# MC_LV.net
KiCad netlist of a schematic drawn in Altium Designer
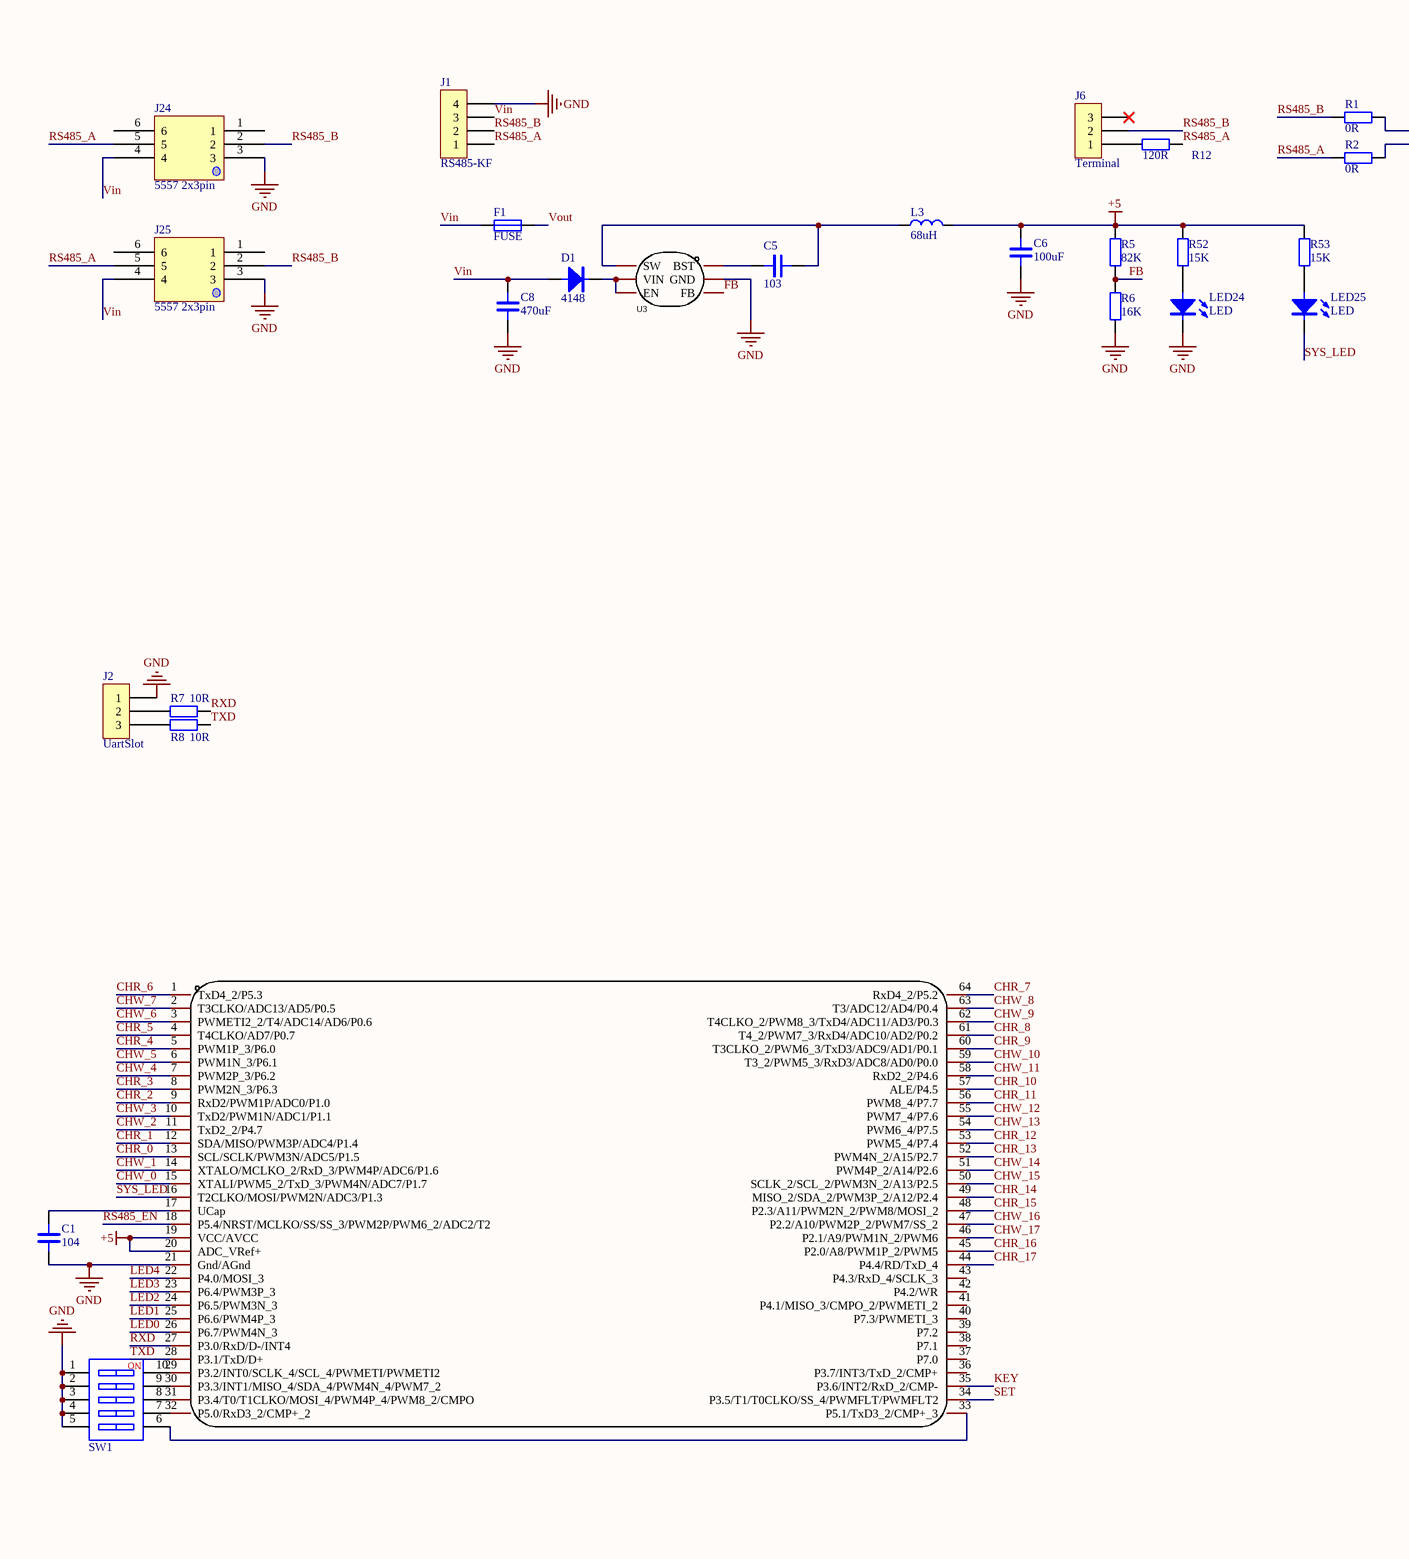
[diagram p0: MC_LV.SchDoc, left]
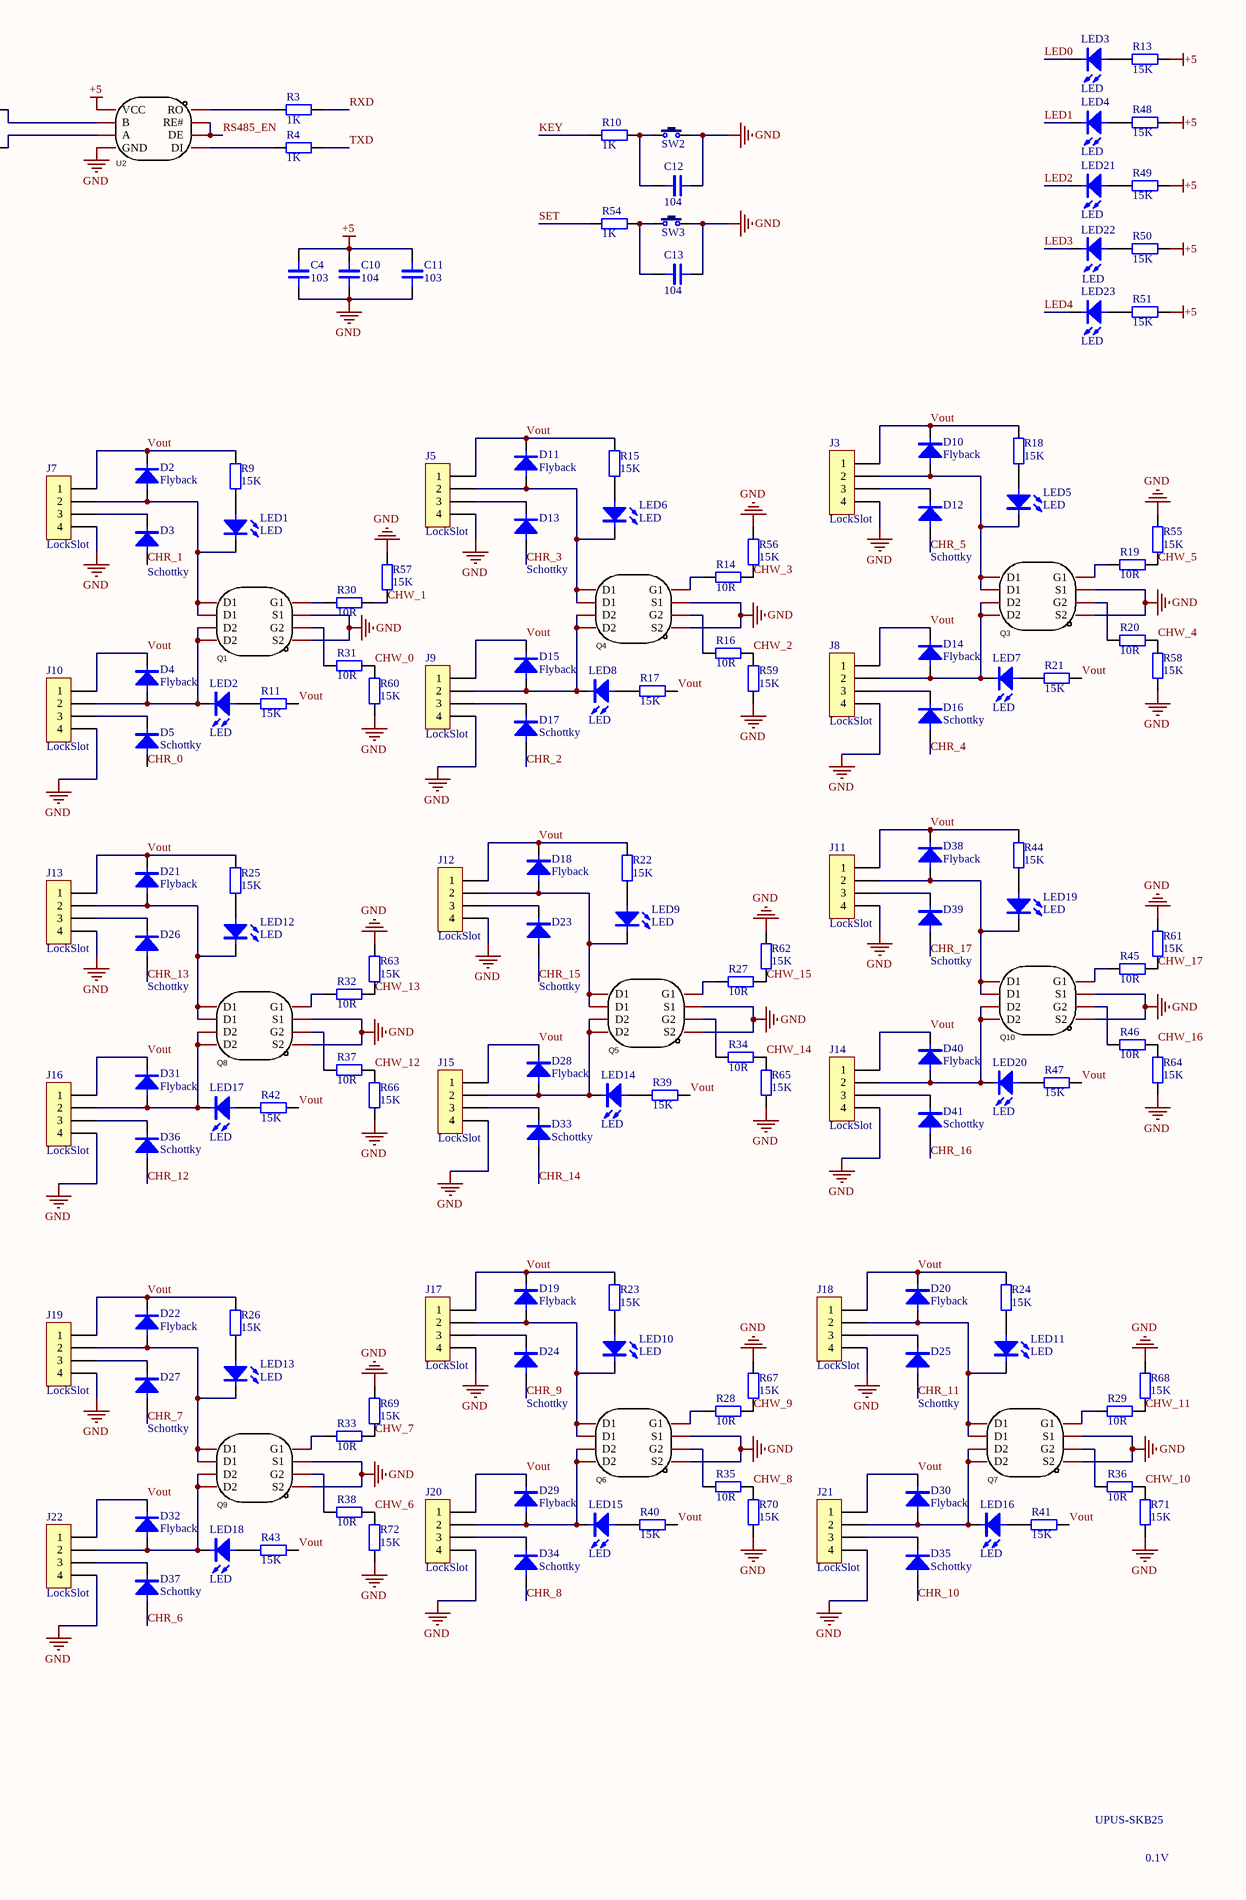
[diagram p1: MC_LV.SchDoc, right]

(export (version "E")
  (design (tool "Eeschema 10.0.6"))
  (components
    (comp (ref "C1")
      (value "104")
      (footprint "LC-0603_C")
      (description "Capacitor")
      (libsource (lib "General") (part "CAP"))
    )
    (comp (ref "C4")
      (value "103")
      (footprint "LC-0603_C")
      (description "Capacitor")
      (libsource (lib "General") (part "CAP"))
    )
    (comp (ref "C5")
      (value "103")
      (footprint "LC-0603_C")
      (description "Capacitor")
      (libsource (lib "General") (part "CAP"))
    )
    (comp (ref "C6")
      (value "100uF")
      (footprint "LC-1206_C")
      (description "Capacitor")
      (libsource (lib "General") (part "CAP"))
    )
    (comp (ref "C8")
      (value "470uF")
      (footprint "CM F(10*10.2)")
      (description "Capacitor")
      (libsource (lib "General") (part "CAP"))
    )
    (comp (ref "C10")
      (value "104")
      (footprint "LC-0603_C")
      (description "Capacitor")
      (libsource (lib "General") (part "CAP"))
    )
    (comp (ref "C11")
      (value "103")
      (footprint "LC-0603_C")
      (description "Capacitor")
      (libsource (lib "General") (part "CAP"))
    )
    (comp (ref "C12")
      (value "104")
      (footprint "LC-0603_C")
      (description "Capacitor")
      (libsource (lib "General") (part "CAP"))
    )
    (comp (ref "C13")
      (value "104")
      (footprint "LC-0603_C")
      (description "Capacitor")
      (libsource (lib "General") (part "CAP"))
    )
    (comp (ref "D1")
      (value "4148")
      (footprint "MINI_MELF (LL34)")
      (description "Diode")
      (libsource (lib "General") (part "ES2x"))
    )
    (comp (ref "D2")
      (value "Flyback")
      (footprint "SOD-123F")
      (description "Diode")
      (libsource (lib "General") (part "ES2x"))
    )
    (comp (ref "D3")
      (value "Schottky")
      (footprint "LC-SOD-523")
      (description "Diode")
      (libsource (lib "General") (part "ES2x"))
    )
    (comp (ref "D4")
      (value "Flyback")
      (footprint "SOD-123F")
      (description "Diode")
      (libsource (lib "General") (part "ES2x"))
    )
    (comp (ref "D5")
      (value "Schottky")
      (footprint "LC-SOD-523")
      (description "Diode")
      (libsource (lib "General") (part "ES2x"))
    )
    (comp (ref "D10")
      (value "Flyback")
      (footprint "SOD-123F")
      (description "Diode")
      (libsource (lib "General") (part "ES2x"))
    )
    (comp (ref "D11")
      (value "Flyback")
      (footprint "SOD-123F")
      (description "Diode")
      (libsource (lib "General") (part "ES2x"))
    )
    (comp (ref "D12")
      (value "Schottky")
      (footprint "LC-SOD-523")
      (description "Diode")
      (libsource (lib "General") (part "ES2x"))
    )
    (comp (ref "D13")
      (value "Schottky")
      (footprint "LC-SOD-523")
      (description "Diode")
      (libsource (lib "General") (part "ES2x"))
    )
    (comp (ref "D14")
      (value "Flyback")
      (footprint "SOD-123F")
      (description "Diode")
      (libsource (lib "General") (part "ES2x"))
    )
    (comp (ref "D15")
      (value "Flyback")
      (footprint "SOD-123F")
      (description "Diode")
      (libsource (lib "General") (part "ES2x"))
    )
    (comp (ref "D16")
      (value "Schottky")
      (footprint "LC-SOD-523")
      (description "Diode")
      (libsource (lib "General") (part "ES2x"))
    )
    (comp (ref "D17")
      (value "Schottky")
      (footprint "LC-SOD-523")
      (description "Diode")
      (libsource (lib "General") (part "ES2x"))
    )
    (comp (ref "D18")
      (value "Flyback")
      (footprint "SOD-123F")
      (description "Diode")
      (libsource (lib "General") (part "ES2x"))
    )
    (comp (ref "D19")
      (value "Flyback")
      (footprint "SOD-123F")
      (description "Diode")
      (libsource (lib "General") (part "ES2x"))
    )
    (comp (ref "D20")
      (value "Flyback")
      (footprint "SOD-123F")
      (description "Diode")
      (libsource (lib "General") (part "ES2x"))
    )
    (comp (ref "D21")
      (value "Flyback")
      (footprint "SOD-123F")
      (description "Diode")
      (libsource (lib "General") (part "ES2x"))
    )
    (comp (ref "D22")
      (value "Flyback")
      (footprint "SOD-123F")
      (description "Diode")
      (libsource (lib "General") (part "ES2x"))
    )
    (comp (ref "D23")
      (value "Schottky")
      (footprint "LC-SOD-523")
      (description "Diode")
      (libsource (lib "General") (part "ES2x"))
    )
    (comp (ref "D24")
      (value "Schottky")
      (footprint "LC-SOD-523")
      (description "Diode")
      (libsource (lib "General") (part "ES2x"))
    )
    (comp (ref "D25")
      (value "Schottky")
      (footprint "LC-SOD-523")
      (description "Diode")
      (libsource (lib "General") (part "ES2x"))
    )
    (comp (ref "D26")
      (value "Schottky")
      (footprint "LC-SOD-523")
      (description "Diode")
      (libsource (lib "General") (part "ES2x"))
    )
    (comp (ref "D27")
      (value "Schottky")
      (footprint "LC-SOD-523")
      (description "Diode")
      (libsource (lib "General") (part "ES2x"))
    )
    (comp (ref "D28")
      (value "Flyback")
      (footprint "SOD-123F")
      (description "Diode")
      (libsource (lib "General") (part "ES2x"))
    )
    (comp (ref "D29")
      (value "Flyback")
      (footprint "SOD-123F")
      (description "Diode")
      (libsource (lib "General") (part "ES2x"))
    )
    (comp (ref "D30")
      (value "Flyback")
      (footprint "SOD-123F")
      (description "Diode")
      (libsource (lib "General") (part "ES2x"))
    )
    (comp (ref "D31")
      (value "Flyback")
      (footprint "SOD-123F")
      (description "Diode")
      (libsource (lib "General") (part "ES2x"))
    )
    (comp (ref "D32")
      (value "Flyback")
      (footprint "SOD-123F")
      (description "Diode")
      (libsource (lib "General") (part "ES2x"))
    )
    (comp (ref "D33")
      (value "Schottky")
      (footprint "LC-SOD-523")
      (description "Diode")
      (libsource (lib "General") (part "ES2x"))
    )
    (comp (ref "D34")
      (value "Schottky")
      (footprint "LC-SOD-523")
      (description "Diode")
      (libsource (lib "General") (part "ES2x"))
    )
    (comp (ref "D35")
      (value "Schottky")
      (footprint "LC-SOD-523")
      (description "Diode")
      (libsource (lib "General") (part "ES2x"))
    )
    (comp (ref "D36")
      (value "Schottky")
      (footprint "LC-SOD-523")
      (description "Diode")
      (libsource (lib "General") (part "ES2x"))
    )
    (comp (ref "D37")
      (value "Schottky")
      (footprint "LC-SOD-523")
      (description "Diode")
      (libsource (lib "General") (part "ES2x"))
    )
    (comp (ref "D38")
      (value "Flyback")
      (footprint "SOD-123F")
      (description "Diode")
      (libsource (lib "General") (part "ES2x"))
    )
    (comp (ref "D39")
      (value "Schottky")
      (footprint "LC-SOD-523")
      (description "Diode")
      (libsource (lib "General") (part "ES2x"))
    )
    (comp (ref "D40")
      (value "Flyback")
      (footprint "SOD-123F")
      (description "Diode")
      (libsource (lib "General") (part "ES2x"))
    )
    (comp (ref "D41")
      (value "Schottky")
      (footprint "LC-SOD-523")
      (description "Diode")
      (libsource (lib "General") (part "ES2x"))
    )
    (comp (ref "F1")
      (value "FUSE")
      (footprint "FUSE-1812")
      (description "30V 3A")
      (libsource (lib "General") (part "FUSE"))
    )
    (comp (ref "J1")
      (value "RS485-KF")
      (footprint "KF128-5.08-4P")
      (description "Connector")
      (libsource (lib "") (part "HDR1x4_1"))
    )
    (comp (ref "J2")
      (value "UartSlot")
      (footprint "XH2.54-3P")
      (description "Connector")
      (libsource (lib "General") (part "HDR1x3"))
    )
    (comp (ref "J3")
      (value "LockSlot")
      (footprint "XH2.54-4P")
      (description "Connector")
      (libsource (lib "General") (part "HDR1x4"))
    )
    (comp (ref "J5")
      (value "LockSlot")
      (footprint "XH2.54-4P")
      (description "Connector")
      (libsource (lib "General") (part "HDR1x4"))
    )
    (comp (ref "J6")
      (value "Terminal")
      (footprint "PIN-3-2.54-1.0")
      (description "Connector")
      (libsource (lib "") (part "HDR1x3_1"))
    )
    (comp (ref "J7")
      (value "LockSlot")
      (footprint "XH2.54-4P")
      (description "Connector")
      (libsource (lib "General") (part "HDR1x4"))
    )
    (comp (ref "J8")
      (value "LockSlot")
      (footprint "XH2.54-4P")
      (description "Connector")
      (libsource (lib "General") (part "HDR1x4"))
    )
    (comp (ref "J9")
      (value "LockSlot")
      (footprint "XH2.54-4P")
      (description "Connector")
      (libsource (lib "General") (part "HDR1x4"))
    )
    (comp (ref "J10")
      (value "LockSlot")
      (footprint "XH2.54-4P")
      (description "Connector")
      (libsource (lib "General") (part "HDR1x4"))
    )
    (comp (ref "J11")
      (value "LockSlot")
      (footprint "XH2.54-4P")
      (description "Connector")
      (libsource (lib "General") (part "HDR1x4"))
    )
    (comp (ref "J12")
      (value "LockSlot")
      (footprint "XH2.54-4P")
      (description "Connector")
      (libsource (lib "General") (part "HDR1x4"))
    )
    (comp (ref "J13")
      (value "LockSlot")
      (footprint "XH2.54-4P")
      (description "Connector")
      (libsource (lib "General") (part "HDR1x4"))
    )
    (comp (ref "J14")
      (value "LockSlot")
      (footprint "XH2.54-4P")
      (description "Connector")
      (libsource (lib "General") (part "HDR1x4"))
    )
    (comp (ref "J15")
      (value "LockSlot")
      (footprint "XH2.54-4P")
      (description "Connector")
      (libsource (lib "General") (part "HDR1x4"))
    )
    (comp (ref "J16")
      (value "LockSlot")
      (footprint "XH2.54-4P")
      (description "Connector")
      (libsource (lib "General") (part "HDR1x4"))
    )
    (comp (ref "J17")
      (value "LockSlot")
      (footprint "XH2.54-4P")
      (description "Connector")
      (libsource (lib "General") (part "HDR1x4"))
    )
    (comp (ref "J18")
      (value "LockSlot")
      (footprint "XH2.54-4P")
      (description "Connector")
      (libsource (lib "General") (part "HDR1x4"))
    )
    (comp (ref "J19")
      (value "LockSlot")
      (footprint "XH2.54-4P")
      (description "Connector")
      (libsource (lib "General") (part "HDR1x4"))
    )
    (comp (ref "J20")
      (value "LockSlot")
      (footprint "XH2.54-4P")
      (description "Connector")
      (libsource (lib "General") (part "HDR1x4"))
    )
    (comp (ref "J21")
      (value "LockSlot")
      (footprint "XH2.54-4P")
      (description "Connector")
      (libsource (lib "General") (part "HDR1x4"))
    )
    (comp (ref "J22")
      (value "LockSlot")
      (footprint "XH2.54-4P")
      (description "Connector")
      (libsource (lib "General") (part "HDR1x4"))
    )
    (comp (ref "J24")
      (value "5557 2x3pin")
      (footprint "5557 2x3pin")
      (libsource (lib "General") (part "5557 2x3pin"))
    )
    (comp (ref "J25")
      (value "5557 2x3pin")
      (footprint "5557 2x3pin")
      (libsource (lib "General") (part "5557 2x3pin"))
    )
    (comp (ref "L3")
      (value "68uH")
      (footprint "CD32")
      (description "Inductance")
      (libsource (lib "General") (part "INDUCTANCE"))
    )
    (comp (ref "LED1") (value "LED") (footprint "LED 0603B") (libsource (lib "General") (part "LED")))
    (comp (ref "LED2") (value "LED") (footprint "LED 0603B") (libsource (lib "General") (part "LED")))
    (comp (ref "LED3") (value "LED") (footprint "LED 0603B") (libsource (lib "General") (part "LED")))
    (comp (ref "LED4") (value "LED") (footprint "LED 0603B") (libsource (lib "General") (part "LED")))
    (comp (ref "LED5") (value "LED") (footprint "LED 0603B") (libsource (lib "General") (part "LED")))
    (comp (ref "LED6") (value "LED") (footprint "LED 0603B") (libsource (lib "General") (part "LED")))
    (comp (ref "LED7") (value "LED") (footprint "LED 0603B") (libsource (lib "General") (part "LED")))
    (comp (ref "LED8") (value "LED") (footprint "LED 0603B") (libsource (lib "General") (part "LED")))
    (comp (ref "LED9") (value "LED") (footprint "LED 0603B") (libsource (lib "General") (part "LED")))
    (comp (ref "LED10") (value "LED") (footprint "LED 0603B") (libsource (lib "General") (part "LED")))
    (comp (ref "LED11") (value "LED") (footprint "LED 0603B") (libsource (lib "General") (part "LED")))
    (comp (ref "LED12") (value "LED") (footprint "LED 0603B") (libsource (lib "General") (part "LED")))
    (comp (ref "LED13") (value "LED") (footprint "LED 0603B") (libsource (lib "General") (part "LED")))
    (comp (ref "LED14") (value "LED") (footprint "LED 0603B") (libsource (lib "General") (part "LED")))
    (comp (ref "LED15") (value "LED") (footprint "LED 0603B") (libsource (lib "General") (part "LED")))
    (comp (ref "LED16") (value "LED") (footprint "LED 0603B") (libsource (lib "General") (part "LED")))
    (comp (ref "LED17") (value "LED") (footprint "LED 0603B") (libsource (lib "General") (part "LED")))
    (comp (ref "LED18") (value "LED") (footprint "LED 0603B") (libsource (lib "General") (part "LED")))
    (comp (ref "LED19") (value "LED") (footprint "LED 0603B") (libsource (lib "General") (part "LED")))
    (comp (ref "LED20") (value "LED") (footprint "LED 0603B") (libsource (lib "General") (part "LED")))
    (comp (ref "LED21") (value "LED") (footprint "LED 0603B") (libsource (lib "General") (part "LED")))
    (comp (ref "LED22") (value "LED") (footprint "LED 0603B") (libsource (lib "General") (part "LED")))
    (comp (ref "LED23") (value "LED") (footprint "LED 0603B") (libsource (lib "General") (part "LED")))
    (comp (ref "LED24") (value "LED") (footprint "LED 0603B") (libsource (lib "General") (part "LED")))
    (comp (ref "LED25") (value "LED") (footprint "LED 0603B") (libsource (lib "General") (part "LED")))
    (comp (ref "Q1")
      (value "NCE6005AS")
      (footprint "SOP8_N")
      (description "Mosfet")
      (fields (field (name "MANUFACTURER") "NCE(无锡新洁能)"))
      (libsource (lib "General") (part "NCE6005AS"))
    )
    (comp (ref "Q3")
      (value "NCE6005AS")
      (footprint "SOP8_N")
      (description "Mosfet")
      (fields (field (name "MANUFACTURER") "NCE(无锡新洁能)"))
      (libsource (lib "General") (part "NCE6005AS"))
    )
    (comp (ref "Q4")
      (value "NCE6005AS")
      (footprint "SOP8_N")
      (description "Mosfet")
      (fields (field (name "MANUFACTURER") "NCE(无锡新洁能)"))
      (libsource (lib "General") (part "NCE6005AS"))
    )
    (comp (ref "Q5")
      (value "NCE6005AS")
      (footprint "SOP8_N")
      (description "Mosfet")
      (fields (field (name "MANUFACTURER") "NCE(无锡新洁能)"))
      (libsource (lib "General") (part "NCE6005AS"))
    )
    (comp (ref "Q6")
      (value "NCE6005AS")
      (footprint "SOP8_N")
      (description "Mosfet")
      (fields (field (name "MANUFACTURER") "NCE(无锡新洁能)"))
      (libsource (lib "General") (part "NCE6005AS"))
    )
    (comp (ref "Q7")
      (value "NCE6005AS")
      (footprint "SOP8_N")
      (description "Mosfet")
      (fields (field (name "MANUFACTURER") "NCE(无锡新洁能)"))
      (libsource (lib "General") (part "NCE6005AS"))
    )
    (comp (ref "Q8")
      (value "NCE6005AS")
      (footprint "SOP8_N")
      (description "Mosfet")
      (fields (field (name "MANUFACTURER") "NCE(无锡新洁能)"))
      (libsource (lib "General") (part "NCE6005AS"))
    )
    (comp (ref "Q9")
      (value "NCE6005AS")
      (footprint "SOP8_N")
      (description "Mosfet")
      (fields (field (name "MANUFACTURER") "NCE(无锡新洁能)"))
      (libsource (lib "General") (part "NCE6005AS"))
    )
    (comp (ref "Q10")
      (value "NCE6005AS")
      (footprint "SOP8_N")
      (description "Mosfet")
      (fields (field (name "MANUFACTURER") "NCE(无锡新洁能)"))
      (libsource (lib "General") (part "NCE6005AS"))
    )
    (comp (ref "R1")
      (value "0R")
      (footprint "LC-0603_R")
      (description "Resistor")
      (libsource (lib "") (part "RES_3"))
    )
    (comp (ref "R2")
      (value "0R")
      (footprint "LC-0603_R")
      (description "Resistor")
      (libsource (lib "") (part "RES_3"))
    )
    (comp (ref "R3")
      (value "1K")
      (footprint "LC-0603_R")
      (description "Resistor")
      (libsource (lib "") (part "RES_3"))
    )
    (comp (ref "R4")
      (value "1K")
      (footprint "LC-0603_R")
      (description "Resistor")
      (libsource (lib "") (part "RES_3"))
    )
    (comp (ref "R5")
      (value "82K")
      (footprint "LC-0603_R")
      (description "Resistor")
      (libsource (lib "") (part "RES_1"))
    )
    (comp (ref "R6")
      (value "16K")
      (footprint "LC-0603_R")
      (description "Resistor")
      (libsource (lib "") (part "RES_1"))
    )
    (comp (ref "R7")
      (value "10R")
      (footprint "LC-0603_R")
      (description "Resistor")
      (libsource (lib "") (part "RES_3"))
    )
    (comp (ref "R8")
      (value "10R")
      (footprint "LC-0603_R")
      (description "Resistor")
      (libsource (lib "") (part "RES_3"))
    )
    (comp (ref "R9")
      (value "15K")
      (footprint "LC-0603_R")
      (description "Resistor")
      (libsource (lib "") (part "RES_1"))
    )
    (comp (ref "R10")
      (value "1K")
      (footprint "LC-0603_R")
      (description "Resistor")
      (libsource (lib "General") (part "RES"))
    )
    (comp (ref "R11")
      (value "15K")
      (footprint "LC-0603_R")
      (description "Resistor")
      (libsource (lib "") (part "RES_3"))
    )
    (comp (ref "R12")
      (value "120R")
      (footprint "LC-0603_R")
      (description "Resistor")
      (libsource (lib "") (part "RES_2"))
    )
    (comp (ref "R13")
      (value "15K")
      (footprint "LC-0603_R")
      (description "Resistor")
      (libsource (lib "") (part "RES_3"))
    )
    (comp (ref "R14")
      (value "10R")
      (footprint "LC-0603_R")
      (description "Resistor")
      (libsource (lib "") (part "RES_2"))
    )
    (comp (ref "R15")
      (value "15K")
      (footprint "LC-0603_R")
      (description "Resistor")
      (libsource (lib "") (part "RES_1"))
    )
    (comp (ref "R16")
      (value "10R")
      (footprint "LC-0603_R")
      (description "Resistor")
      (libsource (lib "") (part "RES_2"))
    )
    (comp (ref "R17")
      (value "15K")
      (footprint "LC-0603_R")
      (description "Resistor")
      (libsource (lib "") (part "RES_3"))
    )
    (comp (ref "R18")
      (value "15K")
      (footprint "LC-0603_R")
      (description "Resistor")
      (libsource (lib "") (part "RES_1"))
    )
    (comp (ref "R19")
      (value "10R")
      (footprint "LC-0603_R")
      (description "Resistor")
      (libsource (lib "") (part "RES_2"))
    )
    (comp (ref "R20")
      (value "10R")
      (footprint "LC-0603_R")
      (description "Resistor")
      (libsource (lib "") (part "RES_2"))
    )
    (comp (ref "R21")
      (value "15K")
      (footprint "LC-0603_R")
      (description "Resistor")
      (libsource (lib "") (part "RES_3"))
    )
    (comp (ref "R22")
      (value "15K")
      (footprint "LC-0603_R")
      (description "Resistor")
      (libsource (lib "") (part "RES_1"))
    )
    (comp (ref "R23")
      (value "15K")
      (footprint "LC-0603_R")
      (description "Resistor")
      (libsource (lib "") (part "RES_1"))
    )
    (comp (ref "R24")
      (value "15K")
      (footprint "LC-0603_R")
      (description "Resistor")
      (libsource (lib "") (part "RES_1"))
    )
    (comp (ref "R25")
      (value "15K")
      (footprint "LC-0603_R")
      (description "Resistor")
      (libsource (lib "") (part "RES_1"))
    )
    (comp (ref "R26")
      (value "15K")
      (footprint "LC-0603_R")
      (description "Resistor")
      (libsource (lib "") (part "RES_1"))
    )
    (comp (ref "R27")
      (value "10R")
      (footprint "LC-0603_R")
      (description "Resistor")
      (libsource (lib "") (part "RES_2"))
    )
    (comp (ref "R28")
      (value "10R")
      (footprint "LC-0603_R")
      (description "Resistor")
      (libsource (lib "") (part "RES_2"))
    )
    (comp (ref "R29")
      (value "10R")
      (footprint "LC-0603_R")
      (description "Resistor")
      (libsource (lib "") (part "RES_2"))
    )
    (comp (ref "R30")
      (value "10R")
      (footprint "LC-0603_R")
      (description "Resistor")
      (libsource (lib "") (part "RES_2"))
    )
    (comp (ref "R31")
      (value "10R")
      (footprint "LC-0603_R")
      (description "Resistor")
      (libsource (lib "") (part "RES_3"))
    )
    (comp (ref "R32")
      (value "10R")
      (footprint "LC-0603_R")
      (description "Resistor")
      (libsource (lib "") (part "RES_2"))
    )
    (comp (ref "R33")
      (value "10R")
      (footprint "LC-0603_R")
      (description "Resistor")
      (libsource (lib "") (part "RES_2"))
    )
    (comp (ref "R34")
      (value "10R")
      (footprint "LC-0603_R")
      (description "Resistor")
      (libsource (lib "") (part "RES_2"))
    )
    (comp (ref "R35")
      (value "10R")
      (footprint "LC-0603_R")
      (description "Resistor")
      (libsource (lib "") (part "RES_2"))
    )
    (comp (ref "R36")
      (value "10R")
      (footprint "LC-0603_R")
      (description "Resistor")
      (libsource (lib "") (part "RES_2"))
    )
    (comp (ref "R37")
      (value "10R")
      (footprint "LC-0603_R")
      (description "Resistor")
      (libsource (lib "") (part "RES_2"))
    )
    (comp (ref "R38")
      (value "10R")
      (footprint "LC-0603_R")
      (description "Resistor")
      (libsource (lib "") (part "RES_2"))
    )
    (comp (ref "R39")
      (value "15K")
      (footprint "LC-0603_R")
      (description "Resistor")
      (libsource (lib "") (part "RES_3"))
    )
    (comp (ref "R40")
      (value "15K")
      (footprint "LC-0603_R")
      (description "Resistor")
      (libsource (lib "") (part "RES_3"))
    )
    (comp (ref "R41")
      (value "15K")
      (footprint "LC-0603_R")
      (description "Resistor")
      (libsource (lib "") (part "RES_3"))
    )
    (comp (ref "R42")
      (value "15K")
      (footprint "LC-0603_R")
      (description "Resistor")
      (libsource (lib "") (part "RES_3"))
    )
    (comp (ref "R43")
      (value "15K")
      (footprint "LC-0603_R")
      (description "Resistor")
      (libsource (lib "") (part "RES_3"))
    )
    (comp (ref "R44")
      (value "15K")
      (footprint "LC-0603_R")
      (description "Resistor")
      (libsource (lib "") (part "RES_1"))
    )
    (comp (ref "R45")
      (value "10R")
      (footprint "LC-0603_R")
      (description "Resistor")
      (libsource (lib "") (part "RES_2"))
    )
    (comp (ref "R46")
      (value "10R")
      (footprint "LC-0603_R")
      (description "Resistor")
      (libsource (lib "") (part "RES_2"))
    )
    (comp (ref "R47")
      (value "15K")
      (footprint "LC-0603_R")
      (description "Resistor")
      (libsource (lib "") (part "RES_3"))
    )
    (comp (ref "R48")
      (value "15K")
      (footprint "LC-0603_R")
      (description "Resistor")
      (libsource (lib "") (part "RES_3"))
    )
    (comp (ref "R49")
      (value "15K")
      (footprint "LC-0603_R")
      (description "Resistor")
      (libsource (lib "") (part "RES_3"))
    )
    (comp (ref "R50")
      (value "15K")
      (footprint "LC-0603_R")
      (description "Resistor")
      (libsource (lib "") (part "RES_3"))
    )
    (comp (ref "R51")
      (value "15K")
      (footprint "LC-0603_R")
      (description "Resistor")
      (libsource (lib "") (part "RES_3"))
    )
    (comp (ref "R52")
      (value "15K")
      (footprint "LC-0603_R")
      (description "Resistor")
      (libsource (lib "") (part "RES_1"))
    )
    (comp (ref "R53")
      (value "15K")
      (footprint "LC-0603_R")
      (description "Resistor")
      (libsource (lib "") (part "RES_1"))
    )
    (comp (ref "R54")
      (value "1K")
      (footprint "LC-0603_R")
      (description "Resistor")
      (libsource (lib "General") (part "RES"))
    )
    (comp (ref "R55")
      (value "15K")
      (footprint "LC-0603_R")
      (description "Resistor")
      (libsource (lib "General") (part "RES"))
    )
    (comp (ref "R56")
      (value "15K")
      (footprint "LC-0603_R")
      (description "Resistor")
      (libsource (lib "General") (part "RES"))
    )
    (comp (ref "R57")
      (value "15K")
      (footprint "LC-0603_R")
      (description "Resistor")
      (libsource (lib "General") (part "RES"))
    )
    (comp (ref "R58")
      (value "15K")
      (footprint "LC-0603_R")
      (description "Resistor")
      (libsource (lib "") (part "RES_1"))
    )
    (comp (ref "R59")
      (value "15K")
      (footprint "LC-0603_R")
      (description "Resistor")
      (libsource (lib "") (part "RES_1"))
    )
    (comp (ref "R60")
      (value "15K")
      (footprint "LC-0603_R")
      (description "Resistor")
      (libsource (lib "") (part "RES_1"))
    )
    (comp (ref "R61")
      (value "15K")
      (footprint "LC-0603_R")
      (description "Resistor")
      (libsource (lib "General") (part "RES"))
    )
    (comp (ref "R62")
      (value "15K")
      (footprint "LC-0603_R")
      (description "Resistor")
      (libsource (lib "General") (part "RES"))
    )
    (comp (ref "R63")
      (value "15K")
      (footprint "LC-0603_R")
      (description "Resistor")
      (libsource (lib "General") (part "RES"))
    )
    (comp (ref "R64")
      (value "15K")
      (footprint "LC-0603_R")
      (description "Resistor")
      (libsource (lib "") (part "RES_1"))
    )
    (comp (ref "R65")
      (value "15K")
      (footprint "LC-0603_R")
      (description "Resistor")
      (libsource (lib "") (part "RES_1"))
    )
    (comp (ref "R66")
      (value "15K")
      (footprint "LC-0603_R")
      (description "Resistor")
      (libsource (lib "") (part "RES_1"))
    )
    (comp (ref "R67")
      (value "15K")
      (footprint "LC-0603_R")
      (description "Resistor")
      (libsource (lib "General") (part "RES"))
    )
    (comp (ref "R68")
      (value "15K")
      (footprint "LC-0603_R")
      (description "Resistor")
      (libsource (lib "General") (part "RES"))
    )
    (comp (ref "R69")
      (value "15K")
      (footprint "LC-0603_R")
      (description "Resistor")
      (libsource (lib "General") (part "RES"))
    )
    (comp (ref "R70")
      (value "15K")
      (footprint "LC-0603_R")
      (description "Resistor")
      (libsource (lib "") (part "RES_1"))
    )
    (comp (ref "R71")
      (value "15K")
      (footprint "LC-0603_R")
      (description "Resistor")
      (libsource (lib "") (part "RES_1"))
    )
    (comp (ref "R72")
      (value "15K")
      (footprint "LC-0603_R")
      (description "Resistor")
      (libsource (lib "") (part "RES_1"))
    )
    (comp (ref "SW1")
      (value "CSW-5P")
      (footprint "SMD-5KEY")
      (description "5路编码开关")
      (fields (field (name "版权归属") "源创客"))
      (libsource (lib "按键-开关") (part "CSW-5P"))
    )
    (comp (ref "SW2")
      (value "3x6x5")
      (footprint "TSW SMD-3*6*2.5")
      (description "3x6轻触开关")
      (fields (field (name "版权归属") "源创客"))
      (libsource (lib "按键-开关") (part "TSW 3x6"))
    )
    (comp (ref "SW3")
      (value "3x6x5")
      (footprint "TSW SMD-3*6*2.5")
      (description "3x6轻触开关")
      (fields (field (name "版权归属") "源创客"))
      (libsource (lib "按键-开关") (part "TSW 3x6"))
    )
    (comp (ref "U1")
      (value "STC8H8K64U-45I-LQFP64_C3013146")
      (footprint "LQFP64 10x10_N")
      (description "MCU")
      (fields
        (field (name "MANUFACTURER") "STC(宏晶)")
        (field (name "MANUFACTURER PART") "STC8H8K64U-45I-LQFP64")
      )
      (libsource (lib "General") (part "STC8H8K64U-45I-LQFP64_C3013146"))
    )
    (comp (ref "U2")
      (value "YD3082EESA")
      (footprint "SOP8_N")
      (description "RS485 Controller")
      (fields (field (name "MANUFACTURER") "GATEMODE(捷茂微)"))
      (libsource (lib "General") (part "YD3082EESA"))
    )
    (comp (ref "U3")
      (value "LGS5145")
      (footprint "SOT23-6L")
      (description "DC-DC")
      (fields (field (name "MANUFACTURER") "Legend-Si(棱晶半导体)"))
      (libsource (lib "General") (part "LGS5145"))
    )
  )
  (nets
    (net (code "1") (name "+5") (class "Default")
      (node (ref "C10") (pin "1") (pinfunction "1_1") (pintype "passive"))
      (node (ref "C11") (pin "1") (pinfunction "1_1") (pintype "passive"))
      (node (ref "C4") (pin "1") (pinfunction "1_1") (pintype "passive"))
      (node (ref "C6") (pin "1") (pinfunction "1_1") (pintype "passive"))
      (node (ref "L3") (pin "2") (pinfunction "2_2") (pintype "passive"))
      (node (ref "R13") (pin "2") (pinfunction "2_2") (pintype "passive"))
      (node (ref "R48") (pin "2") (pinfunction "2_2") (pintype "passive"))
      (node (ref "R49") (pin "2") (pinfunction "2_2") (pintype "passive"))
      (node (ref "R5") (pin "2") (pinfunction "2_2") (pintype "passive"))
      (node (ref "R50") (pin "2") (pinfunction "2_2") (pintype "passive"))
      (node (ref "R51") (pin "2") (pinfunction "2_2") (pintype "passive"))
      (node (ref "R52") (pin "2") (pinfunction "2_2") (pintype "passive"))
      (node (ref "R53") (pin "2") (pinfunction "2_2") (pintype "passive"))
      (node (ref "U1") (pin "19") (pinfunction "VCC/AVCC_19") (pintype "passive"))
      (node (ref "U1") (pin "20") (pinfunction "ADC_VRef+_20") (pintype "passive"))
      (node (ref "U2") (pin "8") (pinfunction "VCC_8") (pintype "passive"))
    )
    (net (code "2") (name "/CHR_0") (class "Default")
      (node (ref "D5") (pin "1") (pinfunction "A_1") (pintype "passive"))
      (node (ref "U1") (pin "13") (pinfunction "SCL/SCLK/PWM3N/ADC5/P1.5_13") (pintype "passive"))
    )
    (net (code "3") (name "/CHR_1") (class "Default")
      (node (ref "D3") (pin "1") (pinfunction "A_1") (pintype "passive"))
      (node (ref "U1") (pin "12") (pinfunction "SDA/MISO/PWM3P/ADC4/P1.4_12") (pintype "passive"))
    )
    (net (code "4") (name "/CHR_2") (class "Default")
      (node (ref "D17") (pin "1") (pinfunction "A_1") (pintype "passive"))
      (node (ref "U1") (pin "9") (pinfunction "RxD2/PWM1P/ADC0/P1.0_9") (pintype "passive"))
    )
    (net (code "5") (name "/CHR_3") (class "Default")
      (node (ref "D13") (pin "1") (pinfunction "A_1") (pintype "passive"))
      (node (ref "U1") (pin "8") (pinfunction "PWM2N_3/P6.3_8") (pintype "passive"))
    )
    (net (code "6") (name "/CHR_4") (class "Default")
      (node (ref "D16") (pin "1") (pinfunction "A_1") (pintype "passive"))
      (node (ref "U1") (pin "5") (pinfunction "PWM1P_3/P6.0_5") (pintype "passive"))
    )
    (net (code "7") (name "/CHR_5") (class "Default")
      (node (ref "D12") (pin "1") (pinfunction "A_1") (pintype "passive"))
      (node (ref "U1") (pin "4") (pinfunction "T4CLKO/AD7/P0.7_4") (pintype "passive"))
    )
    (net (code "8") (name "/CHR_6") (class "Default")
      (node (ref "D37") (pin "1") (pinfunction "A_1") (pintype "passive"))
      (node (ref "U1") (pin "1") (pinfunction "TxD4_2/P5.3_1") (pintype "passive"))
    )
    (net (code "9") (name "/CHR_7") (class "Default")
      (node (ref "D27") (pin "1") (pinfunction "A_1") (pintype "passive"))
      (node (ref "U1") (pin "64") (pinfunction "RxD4_2/P5.2_64") (pintype "passive"))
    )
    (net (code "10") (name "/CHR_8") (class "Default")
      (node (ref "D34") (pin "1") (pinfunction "A_1") (pintype "passive"))
      (node (ref "U1") (pin "61") (pinfunction "T4_2/PWM7_3/RxD4/ADC10/AD2/P0.2_61") (pintype "passive"))
    )
    (net (code "11") (name "/CHR_9") (class "Default")
      (node (ref "D24") (pin "1") (pinfunction "A_1") (pintype "passive"))
      (node (ref "U1") (pin "60") (pinfunction "T3CLKO_2/PWM6_3/TxD3/ADC9/AD1/P0.1_60") (pintype "passive"))
    )
    (net (code "12") (name "/CHR_10") (class "Default")
      (node (ref "D35") (pin "1") (pinfunction "A_1") (pintype "passive"))
      (node (ref "U1") (pin "57") (pinfunction "ALE/P4.5_57") (pintype "passive"))
    )
    (net (code "13") (name "/CHR_11") (class "Default")
      (node (ref "D25") (pin "1") (pinfunction "A_1") (pintype "passive"))
      (node (ref "U1") (pin "56") (pinfunction "PWM8_4/P7.7_56") (pintype "passive"))
    )
    (net (code "14") (name "/CHR_12") (class "Default")
      (node (ref "D36") (pin "1") (pinfunction "A_1") (pintype "passive"))
      (node (ref "U1") (pin "53") (pinfunction "PWM5_4/P7.4_53") (pintype "passive"))
    )
    (net (code "15") (name "/CHR_13") (class "Default")
      (node (ref "D26") (pin "1") (pinfunction "A_1") (pintype "passive"))
      (node (ref "U1") (pin "52") (pinfunction "PWM4N_2/A15/P2.7_52") (pintype "passive"))
    )
    (net (code "16") (name "/CHR_14") (class "Default")
      (node (ref "D33") (pin "1") (pinfunction "A_1") (pintype "passive"))
      (node (ref "U1") (pin "49") (pinfunction "MISO_2/SDA_2/PWM3P_2/A12/P2.4_49") (pintype "passive"))
    )
    (net (code "17") (name "/CHR_15") (class "Default")
      (node (ref "D23") (pin "1") (pinfunction "A_1") (pintype "passive"))
      (node (ref "U1") (pin "48") (pinfunction "P2.3/A11/PWM2N_2/PWM8/MOSI_2_48") (pintype "passive"))
    )
    (net (code "18") (name "/CHR_16") (class "Default")
      (node (ref "D41") (pin "1") (pinfunction "A_1") (pintype "passive"))
      (node (ref "U1") (pin "45") (pinfunction "P2.0/A8/PWM1P_2/PWM5_45") (pintype "passive"))
    )
    (net (code "19") (name "/CHR_17") (class "Default")
      (node (ref "D39") (pin "1") (pinfunction "A_1") (pintype "passive"))
      (node (ref "U1") (pin "44") (pinfunction "P4.4/RD/TxD_4_44") (pintype "passive"))
    )
    (net (code "20") (name "/CHW_0") (class "Default")
      (node (ref "R31") (pin "2") (pinfunction "2_2") (pintype "passive"))
      (node (ref "R60") (pin "2") (pinfunction "2_2") (pintype "passive"))
      (node (ref "U1") (pin "15") (pinfunction "XTALI/PWM5_2/TxD_3/PWM4N/ADC7/P1.7_15") (pintype "passive"))
    )
    (net (code "21") (name "/CHW_1") (class "Default")
      (node (ref "R30") (pin "1") (pinfunction "1_1") (pintype "passive"))
      (node (ref "R57") (pin "2") (pinfunction "2_2") (pintype "passive"))
      (node (ref "U1") (pin "14") (pinfunction "XTALO/MCLKO_2/RxD_3/PWM4P/ADC6/P1.6_14") (pintype "passive"))
    )
    (net (code "22") (name "/CHW_2") (class "Default")
      (node (ref "R16") (pin "1") (pinfunction "1_1") (pintype "passive"))
      (node (ref "R59") (pin "2") (pinfunction "2_2") (pintype "passive"))
      (node (ref "U1") (pin "11") (pinfunction "TxD2_2/P4.7_11") (pintype "passive"))
    )
    (net (code "23") (name "/CHW_3") (class "Default")
      (node (ref "R14") (pin "1") (pinfunction "1_1") (pintype "passive"))
      (node (ref "R56") (pin "2") (pinfunction "2_2") (pintype "passive"))
      (node (ref "U1") (pin "10") (pinfunction "TxD2/PWM1N/ADC1/P1.1_10") (pintype "passive"))
    )
    (net (code "24") (name "/CHW_4") (class "Default")
      (node (ref "R20") (pin "1") (pinfunction "1_1") (pintype "passive"))
      (node (ref "R58") (pin "2") (pinfunction "2_2") (pintype "passive"))
      (node (ref "U1") (pin "7") (pinfunction "PWM2P_3/P6.2_7") (pintype "passive"))
    )
    (net (code "25") (name "/CHW_5") (class "Default")
      (node (ref "R19") (pin "1") (pinfunction "1_1") (pintype "passive"))
      (node (ref "R55") (pin "2") (pinfunction "2_2") (pintype "passive"))
      (node (ref "U1") (pin "6") (pinfunction "PWM1N_3/P6.1_6") (pintype "passive"))
    )
    (net (code "26") (name "/CHW_6") (class "Default")
      (node (ref "R38") (pin "1") (pinfunction "1_1") (pintype "passive"))
      (node (ref "R72") (pin "2") (pinfunction "2_2") (pintype "passive"))
      (node (ref "U1") (pin "3") (pinfunction "PWMETI2_2/T4/ADC14/AD6/P0.6_3") (pintype "passive"))
    )
    (net (code "27") (name "/CHW_7") (class "Default")
      (node (ref "R33") (pin "1") (pinfunction "1_1") (pintype "passive"))
      (node (ref "R69") (pin "2") (pinfunction "2_2") (pintype "passive"))
      (node (ref "U1") (pin "2") (pinfunction "T3CLKO/ADC13/AD5/P0.5_2") (pintype "passive"))
    )
    (net (code "28") (name "/CHW_8") (class "Default")
      (node (ref "R35") (pin "1") (pinfunction "1_1") (pintype "passive"))
      (node (ref "R70") (pin "2") (pinfunction "2_2") (pintype "passive"))
      (node (ref "U1") (pin "63") (pinfunction "T3/ADC12/AD4/P0.4_63") (pintype "passive"))
    )
    (net (code "29") (name "/CHW_9") (class "Default")
      (node (ref "R28") (pin "1") (pinfunction "1_1") (pintype "passive"))
      (node (ref "R67") (pin "2") (pinfunction "2_2") (pintype "passive"))
      (node (ref "U1") (pin "62") (pinfunction "T4CLKO_2/PWM8_3/TxD4/ADC11/AD3/P0.3_62") (pintype "passive"))
    )
    (net (code "30") (name "/CHW_10") (class "Default")
      (node (ref "R36") (pin "1") (pinfunction "1_1") (pintype "passive"))
      (node (ref "R71") (pin "2") (pinfunction "2_2") (pintype "passive"))
      (node (ref "U1") (pin "59") (pinfunction "T3_2/PWM5_3/RxD3/ADC8/AD0/P0.0_59") (pintype "passive"))
    )
    (net (code "31") (name "/CHW_11") (class "Default")
      (node (ref "R29") (pin "1") (pinfunction "1_1") (pintype "passive"))
      (node (ref "R68") (pin "2") (pinfunction "2_2") (pintype "passive"))
      (node (ref "U1") (pin "58") (pinfunction "RxD2_2/P4.6_58") (pintype "passive"))
    )
    (net (code "32") (name "/CHW_12") (class "Default")
      (node (ref "R37") (pin "1") (pinfunction "1_1") (pintype "passive"))
      (node (ref "R66") (pin "2") (pinfunction "2_2") (pintype "passive"))
      (node (ref "U1") (pin "55") (pinfunction "PWM7_4/P7.6_55") (pintype "passive"))
    )
    (net (code "33") (name "/CHW_13") (class "Default")
      (node (ref "R32") (pin "1") (pinfunction "1_1") (pintype "passive"))
      (node (ref "R63") (pin "2") (pinfunction "2_2") (pintype "passive"))
      (node (ref "U1") (pin "54") (pinfunction "PWM6_4/P7.5_54") (pintype "passive"))
    )
    (net (code "34") (name "/CHW_14") (class "Default")
      (node (ref "R34") (pin "1") (pinfunction "1_1") (pintype "passive"))
      (node (ref "R65") (pin "2") (pinfunction "2_2") (pintype "passive"))
      (node (ref "U1") (pin "51") (pinfunction "PWM4P_2/A14/P2.6_51") (pintype "passive"))
    )
    (net (code "35") (name "/CHW_15") (class "Default")
      (node (ref "R27") (pin "1") (pinfunction "1_1") (pintype "passive"))
      (node (ref "R62") (pin "2") (pinfunction "2_2") (pintype "passive"))
      (node (ref "U1") (pin "50") (pinfunction "SCLK_2/SCL_2/PWM3N_2/A13/P2.5_50") (pintype "passive"))
    )
    (net (code "36") (name "/CHW_16") (class "Default")
      (node (ref "R46") (pin "1") (pinfunction "1_1") (pintype "passive"))
      (node (ref "R64") (pin "2") (pinfunction "2_2") (pintype "passive"))
      (node (ref "U1") (pin "47") (pinfunction "P2.2/A10/PWM2P_2/PWM7/SS_2_47") (pintype "passive"))
    )
    (net (code "37") (name "/CHW_17") (class "Default")
      (node (ref "R45") (pin "1") (pinfunction "1_1") (pintype "passive"))
      (node (ref "R61") (pin "2") (pinfunction "2_2") (pintype "passive"))
      (node (ref "U1") (pin "46") (pinfunction "P2.1/A9/PWM1N_2/PWM6_46") (pintype "passive"))
    )
    (net (code "38") (name "/FB") (class "Default")
      (node (ref "R5") (pin "1") (pinfunction "1_1") (pintype "passive"))
      (node (ref "R6") (pin "2") (pinfunction "2_2") (pintype "passive"))
      (node (ref "U3") (pin "3") (pinfunction "FB_3") (pintype "passive"))
    )
    (net (code "39") (name "/KEY") (class "Default")
      (node (ref "R10") (pin "2") (pinfunction "2_2") (pintype "passive"))
      (node (ref "U1") (pin "35") (pinfunction "P3.6/INT2/RxD_2/CMP-_35") (pintype "passive"))
    )
    (net (code "40") (name "/LED0") (class "Default")
      (node (ref "LED3") (pin "2") (pinfunction "C_2") (pintype "passive"))
      (node (ref "U1") (pin "26") (pinfunction "P6.7/PWM4N_3_26") (pintype "passive"))
    )
    (net (code "41") (name "/LED1") (class "Default")
      (node (ref "LED4") (pin "2") (pinfunction "C_2") (pintype "passive"))
      (node (ref "U1") (pin "25") (pinfunction "P6.6/PWM4P_3_25") (pintype "passive"))
    )
    (net (code "42") (name "/LED2") (class "Default")
      (node (ref "LED21") (pin "2") (pinfunction "C_2") (pintype "passive"))
      (node (ref "U1") (pin "24") (pinfunction "P6.5/PWM3N_3_24") (pintype "passive"))
    )
    (net (code "43") (name "/LED3") (class "Default")
      (node (ref "LED22") (pin "2") (pinfunction "C_2") (pintype "passive"))
      (node (ref "U1") (pin "23") (pinfunction "P6.4/PWM3P_3_23") (pintype "passive"))
    )
    (net (code "44") (name "/LED4") (class "Default")
      (node (ref "LED23") (pin "2") (pinfunction "C_2") (pintype "passive"))
      (node (ref "U1") (pin "22") (pinfunction "P4.0/MOSI_3_22") (pintype "passive"))
    )
    (net (code "45") (name "/RS485_A") (class "Default")
      (node (ref "J1") (pin "1") (pinfunction "1_1") (pintype "passive"))
      (node (ref "J24") (pin "5") (pinfunction "5_5") (pintype "passive"))
      (node (ref "J25") (pin "5") (pinfunction "5_5") (pintype "passive"))
      (node (ref "R12") (pin "1") (pinfunction "1_1") (pintype "passive"))
      (node (ref "R2") (pin "1") (pinfunction "1_1") (pintype "passive"))
    )
    (net (code "46") (name "/RS485_B") (class "Default")
      (node (ref "J1") (pin "2") (pinfunction "2_2") (pintype "passive"))
      (node (ref "J24") (pin "2") (pinfunction "2_2") (pintype "passive"))
      (node (ref "J25") (pin "2") (pinfunction "2_2") (pintype "passive"))
      (node (ref "J6") (pin "2") (pinfunction "2_2") (pintype "passive"))
      (node (ref "R1") (pin "1") (pinfunction "1_1") (pintype "passive"))
    )
    (net (code "47") (name "/RS485_EN") (class "Default")
      (node (ref "U1") (pin "18") (pinfunction "P5.4/NRST/MCLKO/SS/SS_3/PWM2P/PWM6_2/ADC2/T2_18") (pintype "passive"))
      (node (ref "U2") (pin "2") (pinfunction "RE#_2") (pintype "passive"))
      (node (ref "U2") (pin "3") (pinfunction "DE_3") (pintype "passive"))
    )
    (net (code "48") (name "/RXD") (class "Default")
      (node (ref "R3") (pin "2") (pinfunction "2_2") (pintype "passive"))
      (node (ref "R7") (pin "2") (pinfunction "2_2") (pintype "passive"))
      (node (ref "U1") (pin "27") (pinfunction "P3.0/RxD/D-/INT4_27") (pintype "passive"))
    )
    (net (code "49") (name "/SET") (class "Default")
      (node (ref "R54") (pin "2") (pinfunction "2_2") (pintype "passive"))
      (node (ref "U1") (pin "34") (pinfunction "P3.5/T1/T0CLKO/SS_4/PWMFLT/PWMFLT2_34") (pintype "passive"))
    )
    (net (code "50") (name "/SYS_LED") (class "Default")
      (node (ref "LED25") (pin "2") (pinfunction "C_2") (pintype "passive"))
      (node (ref "U1") (pin "16") (pinfunction "T2CLKO/MOSI/PWM2N/ADC3/P1.3_16") (pintype "passive"))
    )
    (net (code "51") (name "/TXD") (class "Default")
      (node (ref "R4") (pin "2") (pinfunction "2_2") (pintype "passive"))
      (node (ref "R8") (pin "2") (pinfunction "2_2") (pintype "passive"))
      (node (ref "U1") (pin "28") (pinfunction "P3.1/TxD/D+_28") (pintype "passive"))
    )
    (net (code "52") (name "/Vin") (class "Default")
      (node (ref "C8") (pin "1") (pinfunction "1_1") (pintype "passive"))
      (node (ref "D1") (pin "1") (pinfunction "A_1") (pintype "passive"))
      (node (ref "F1") (pin "1") (pinfunction "1_1") (pintype "passive"))
      (node (ref "J1") (pin "3") (pinfunction "3_3") (pintype "passive"))
      (node (ref "J24") (pin "4") (pinfunction "4_4") (pintype "passive"))
      (node (ref "J25") (pin "4") (pinfunction "4_4") (pintype "passive"))
    )
    (net (code "53") (name "/Vout") (class "Default")
      (node (ref "D10") (pin "2") (pinfunction "C_2") (pintype "passive"))
      (node (ref "D11") (pin "2") (pinfunction "C_2") (pintype "passive"))
      (node (ref "D14") (pin "2") (pinfunction "C_2") (pintype "passive"))
      (node (ref "D15") (pin "2") (pinfunction "C_2") (pintype "passive"))
      (node (ref "D18") (pin "2") (pinfunction "C_2") (pintype "passive"))
      (node (ref "D19") (pin "2") (pinfunction "C_2") (pintype "passive"))
      (node (ref "D2") (pin "2") (pinfunction "C_2") (pintype "passive"))
      (node (ref "D20") (pin "2") (pinfunction "C_2") (pintype "passive"))
      (node (ref "D21") (pin "2") (pinfunction "C_2") (pintype "passive"))
      (node (ref "D22") (pin "2") (pinfunction "C_2") (pintype "passive"))
      (node (ref "D28") (pin "2") (pinfunction "C_2") (pintype "passive"))
      (node (ref "D29") (pin "2") (pinfunction "C_2") (pintype "passive"))
      (node (ref "D30") (pin "2") (pinfunction "C_2") (pintype "passive"))
      (node (ref "D31") (pin "2") (pinfunction "C_2") (pintype "passive"))
      (node (ref "D32") (pin "2") (pinfunction "C_2") (pintype "passive"))
      (node (ref "D38") (pin "2") (pinfunction "C_2") (pintype "passive"))
      (node (ref "D4") (pin "2") (pinfunction "C_2") (pintype "passive"))
      (node (ref "D40") (pin "2") (pinfunction "C_2") (pintype "passive"))
      (node (ref "F1") (pin "2") (pinfunction "2_2") (pintype "passive"))
      (node (ref "J10") (pin "1") (pinfunction "1_1") (pintype "passive"))
      (node (ref "J11") (pin "1") (pinfunction "1_1") (pintype "passive"))
      (node (ref "J12") (pin "1") (pinfunction "1_1") (pintype "passive"))
      (node (ref "J13") (pin "1") (pinfunction "1_1") (pintype "passive"))
      (node (ref "J14") (pin "1") (pinfunction "1_1") (pintype "passive"))
      (node (ref "J15") (pin "1") (pinfunction "1_1") (pintype "passive"))
      (node (ref "J16") (pin "1") (pinfunction "1_1") (pintype "passive"))
      (node (ref "J17") (pin "1") (pinfunction "1_1") (pintype "passive"))
      (node (ref "J18") (pin "1") (pinfunction "1_1") (pintype "passive"))
      (node (ref "J19") (pin "1") (pinfunction "1_1") (pintype "passive"))
      (node (ref "J20") (pin "1") (pinfunction "1_1") (pintype "passive"))
      (node (ref "J21") (pin "1") (pinfunction "1_1") (pintype "passive"))
      (node (ref "J22") (pin "1") (pinfunction "1_1") (pintype "passive"))
      (node (ref "J3") (pin "1") (pinfunction "1_1") (pintype "passive"))
      (node (ref "J5") (pin "1") (pinfunction "1_1") (pintype "passive"))
      (node (ref "J7") (pin "1") (pinfunction "1_1") (pintype "passive"))
      (node (ref "J8") (pin "1") (pinfunction "1_1") (pintype "passive"))
      (node (ref "J9") (pin "1") (pinfunction "1_1") (pintype "passive"))
      (node (ref "R11") (pin "2") (pinfunction "2_2") (pintype "passive"))
      (node (ref "R15") (pin "2") (pinfunction "2_2") (pintype "passive"))
      (node (ref "R17") (pin "2") (pinfunction "2_2") (pintype "passive"))
      (node (ref "R18") (pin "2") (pinfunction "2_2") (pintype "passive"))
      (node (ref "R21") (pin "2") (pinfunction "2_2") (pintype "passive"))
      (node (ref "R22") (pin "2") (pinfunction "2_2") (pintype "passive"))
      (node (ref "R23") (pin "2") (pinfunction "2_2") (pintype "passive"))
      (node (ref "R24") (pin "2") (pinfunction "2_2") (pintype "passive"))
      (node (ref "R25") (pin "2") (pinfunction "2_2") (pintype "passive"))
      (node (ref "R26") (pin "2") (pinfunction "2_2") (pintype "passive"))
      (node (ref "R39") (pin "2") (pinfunction "2_2") (pintype "passive"))
      (node (ref "R40") (pin "2") (pinfunction "2_2") (pintype "passive"))
      (node (ref "R41") (pin "2") (pinfunction "2_2") (pintype "passive"))
      (node (ref "R42") (pin "2") (pinfunction "2_2") (pintype "passive"))
      (node (ref "R43") (pin "2") (pinfunction "2_2") (pintype "passive"))
      (node (ref "R44") (pin "2") (pinfunction "2_2") (pintype "passive"))
      (node (ref "R47") (pin "2") (pinfunction "2_2") (pintype "passive"))
      (node (ref "R9") (pin "2") (pinfunction "2_2") (pintype "passive"))
    )
    (net (code "54") (name "GND") (class "Default")
      (node (ref "C1") (pin "2") (pinfunction "2_2") (pintype "passive"))
      (node (ref "C10") (pin "2") (pinfunction "2_2") (pintype "passive"))
      (node (ref "C11") (pin "2") (pinfunction "2_2") (pintype "passive"))
      (node (ref "C12") (pin "2") (pinfunction "2_2") (pintype "passive"))
      (node (ref "C13") (pin "2") (pinfunction "2_2") (pintype "passive"))
      (node (ref "C4") (pin "2") (pinfunction "2_2") (pintype "passive"))
      (node (ref "C6") (pin "2") (pinfunction "2_2") (pintype "passive"))
      (node (ref "C8") (pin "2") (pinfunction "2_2") (pintype "passive"))
      (node (ref "J1") (pin "4") (pinfunction "4_4") (pintype "passive"))
      (node (ref "J10") (pin "4") (pinfunction "4_4") (pintype "passive"))
      (node (ref "J11") (pin "4") (pinfunction "4_4") (pintype "passive"))
      (node (ref "J12") (pin "4") (pinfunction "4_4") (pintype "passive"))
      (node (ref "J13") (pin "4") (pinfunction "4_4") (pintype "passive"))
      (node (ref "J14") (pin "4") (pinfunction "4_4") (pintype "passive"))
      (node (ref "J15") (pin "4") (pinfunction "4_4") (pintype "passive"))
      (node (ref "J16") (pin "4") (pinfunction "4_4") (pintype "passive"))
      (node (ref "J17") (pin "4") (pinfunction "4_4") (pintype "passive"))
      (node (ref "J18") (pin "4") (pinfunction "4_4") (pintype "passive"))
      (node (ref "J19") (pin "4") (pinfunction "4_4") (pintype "passive"))
      (node (ref "J2") (pin "1") (pinfunction "1_1") (pintype "passive"))
      (node (ref "J20") (pin "4") (pinfunction "4_4") (pintype "passive"))
      (node (ref "J21") (pin "4") (pinfunction "4_4") (pintype "passive"))
      (node (ref "J22") (pin "4") (pinfunction "4_4") (pintype "passive"))
      (node (ref "J24") (pin "3") (pinfunction "3_3") (pintype "passive"))
      (node (ref "J25") (pin "3") (pinfunction "3_3") (pintype "passive"))
      (node (ref "J3") (pin "4") (pinfunction "4_4") (pintype "passive"))
      (node (ref "J5") (pin "4") (pinfunction "4_4") (pintype "passive"))
      (node (ref "J7") (pin "4") (pinfunction "4_4") (pintype "passive"))
      (node (ref "J8") (pin "4") (pinfunction "4_4") (pintype "passive"))
      (node (ref "J9") (pin "4") (pinfunction "4_4") (pintype "passive"))
      (node (ref "LED24") (pin "2") (pinfunction "C_2") (pintype "passive"))
      (node (ref "Q1") (pin "1") (pinfunction "S2_1") (pintype "passive"))
      (node (ref "Q1") (pin "3") (pinfunction "S1_3") (pintype "passive"))
      (node (ref "Q10") (pin "1") (pinfunction "S2_1") (pintype "passive"))
      (node (ref "Q10") (pin "3") (pinfunction "S1_3") (pintype "passive"))
      (node (ref "Q3") (pin "1") (pinfunction "S2_1") (pintype "passive"))
      (node (ref "Q3") (pin "3") (pinfunction "S1_3") (pintype "passive"))
      (node (ref "Q4") (pin "1") (pinfunction "S2_1") (pintype "passive"))
      (node (ref "Q4") (pin "3") (pinfunction "S1_3") (pintype "passive"))
      (node (ref "Q5") (pin "1") (pinfunction "S2_1") (pintype "passive"))
      (node (ref "Q5") (pin "3") (pinfunction "S1_3") (pintype "passive"))
      (node (ref "Q6") (pin "1") (pinfunction "S2_1") (pintype "passive"))
      (node (ref "Q6") (pin "3") (pinfunction "S1_3") (pintype "passive"))
      (node (ref "Q7") (pin "1") (pinfunction "S2_1") (pintype "passive"))
      (node (ref "Q7") (pin "3") (pinfunction "S1_3") (pintype "passive"))
      (node (ref "Q8") (pin "1") (pinfunction "S2_1") (pintype "passive"))
      (node (ref "Q8") (pin "3") (pinfunction "S1_3") (pintype "passive"))
      (node (ref "Q9") (pin "1") (pinfunction "S2_1") (pintype "passive"))
      (node (ref "Q9") (pin "3") (pinfunction "S1_3") (pintype "passive"))
      (node (ref "R55") (pin "1") (pinfunction "1_1") (pintype "passive"))
      (node (ref "R56") (pin "1") (pinfunction "1_1") (pintype "passive"))
      (node (ref "R57") (pin "1") (pinfunction "1_1") (pintype "passive"))
      (node (ref "R58") (pin "1") (pinfunction "1_1") (pintype "passive"))
      (node (ref "R59") (pin "1") (pinfunction "1_1") (pintype "passive"))
      (node (ref "R6") (pin "1") (pinfunction "1_1") (pintype "passive"))
      (node (ref "R60") (pin "1") (pinfunction "1_1") (pintype "passive"))
      (node (ref "R61") (pin "1") (pinfunction "1_1") (pintype "passive"))
      (node (ref "R62") (pin "1") (pinfunction "1_1") (pintype "passive"))
      (node (ref "R63") (pin "1") (pinfunction "1_1") (pintype "passive"))
      (node (ref "R64") (pin "1") (pinfunction "1_1") (pintype "passive"))
      (node (ref "R65") (pin "1") (pinfunction "1_1") (pintype "passive"))
      (node (ref "R66") (pin "1") (pinfunction "1_1") (pintype "passive"))
      (node (ref "R67") (pin "1") (pinfunction "1_1") (pintype "passive"))
      (node (ref "R68") (pin "1") (pinfunction "1_1") (pintype "passive"))
      (node (ref "R69") (pin "1") (pinfunction "1_1") (pintype "passive"))
      (node (ref "R70") (pin "1") (pinfunction "1_1") (pintype "passive"))
      (node (ref "R71") (pin "1") (pinfunction "1_1") (pintype "passive"))
      (node (ref "R72") (pin "1") (pinfunction "1_1") (pintype "passive"))
      (node (ref "SW1") (pin "1") (pinfunction "1_1") (pintype "passive"))
      (node (ref "SW1") (pin "2") (pinfunction "2_2") (pintype "passive"))
      (node (ref "SW1") (pin "3") (pinfunction "3_3") (pintype "passive"))
      (node (ref "SW1") (pin "4") (pinfunction "4_4") (pintype "passive"))
      (node (ref "SW1") (pin "5") (pinfunction "5_5") (pintype "passive"))
      (node (ref "SW2") (pin "1") (pinfunction "1_1") (pintype "passive"))
      (node (ref "SW3") (pin "1") (pinfunction "1_1") (pintype "passive"))
      (node (ref "U1") (pin "21") (pinfunction "Gnd/AGnd_21") (pintype "passive"))
      (node (ref "U2") (pin "5") (pinfunction "GND_5") (pintype "passive"))
      (node (ref "U3") (pin "2") (pinfunction "GND_2") (pintype "passive"))
    )
    (net (code "55") (name "Net-(C12-Pad1)") (class "Default")
      (node (ref "C12") (pin "1") (pinfunction "1_1") (pintype "passive"))
      (node (ref "R10") (pin "1") (pinfunction "1_1") (pintype "passive"))
      (node (ref "SW2") (pin "2") (pinfunction "2_2") (pintype "passive"))
    )
    (net (code "56") (name "Net-(C13-Pad1)") (class "Default")
      (node (ref "C13") (pin "1") (pinfunction "1_1") (pintype "passive"))
      (node (ref "R54") (pin "1") (pinfunction "1_1") (pintype "passive"))
      (node (ref "SW3") (pin "2") (pinfunction "2_2") (pintype "passive"))
    )
    (net (code "57") (name "Net-(D1-C)") (class "Default")
      (node (ref "D1") (pin "2") (pinfunction "C_2") (pintype "passive"))
      (node (ref "U3") (pin "4") (pinfunction "EN_4") (pintype "passive"))
      (node (ref "U3") (pin "5") (pinfunction "VIN_5") (pintype "passive"))
    )
    (net (code "58") (name "Net-(D2-A)") (class "Default")
      (node (ref "D2") (pin "1") (pinfunction "A_1") (pintype "passive"))
      (node (ref "J7") (pin "2") (pinfunction "2_2") (pintype "passive"))
      (node (ref "LED1") (pin "2") (pinfunction "C_2") (pintype "passive"))
      (node (ref "Q1") (pin "5") (pinfunction "D1_5") (pintype "passive"))
      (node (ref "Q1") (pin "6") (pinfunction "D1_6") (pintype "passive"))
    )
    (net (code "59") (name "Net-(D3-C)") (class "Default")
      (node (ref "D3") (pin "2") (pinfunction "C_2") (pintype "passive"))
      (node (ref "J7") (pin "3") (pinfunction "3_3") (pintype "passive"))
    )
    (net (code "60") (name "Net-(D4-A)") (class "Default")
      (node (ref "D4") (pin "1") (pinfunction "A_1") (pintype "passive"))
      (node (ref "J10") (pin "2") (pinfunction "2_2") (pintype "passive"))
      (node (ref "LED2") (pin "2") (pinfunction "C_2") (pintype "passive"))
      (node (ref "Q1") (pin "7") (pinfunction "D2_7") (pintype "passive"))
      (node (ref "Q1") (pin "8") (pinfunction "D2_8") (pintype "passive"))
    )
    (net (code "61") (name "Net-(D5-C)") (class "Default")
      (node (ref "D5") (pin "2") (pinfunction "C_2") (pintype "passive"))
      (node (ref "J10") (pin "3") (pinfunction "3_3") (pintype "passive"))
    )
    (net (code "62") (name "Net-(D10-A)") (class "Default")
      (node (ref "D10") (pin "1") (pinfunction "A_1") (pintype "passive"))
      (node (ref "J3") (pin "2") (pinfunction "2_2") (pintype "passive"))
      (node (ref "LED5") (pin "2") (pinfunction "C_2") (pintype "passive"))
      (node (ref "Q3") (pin "5") (pinfunction "D1_5") (pintype "passive"))
      (node (ref "Q3") (pin "6") (pinfunction "D1_6") (pintype "passive"))
    )
    (net (code "63") (name "Net-(D11-A)") (class "Default")
      (node (ref "D11") (pin "1") (pinfunction "A_1") (pintype "passive"))
      (node (ref "J5") (pin "2") (pinfunction "2_2") (pintype "passive"))
      (node (ref "LED6") (pin "2") (pinfunction "C_2") (pintype "passive"))
      (node (ref "Q4") (pin "5") (pinfunction "D1_5") (pintype "passive"))
      (node (ref "Q4") (pin "6") (pinfunction "D1_6") (pintype "passive"))
    )
    (net (code "64") (name "Net-(D12-C)") (class "Default")
      (node (ref "D12") (pin "2") (pinfunction "C_2") (pintype "passive"))
      (node (ref "J3") (pin "3") (pinfunction "3_3") (pintype "passive"))
    )
    (net (code "65") (name "Net-(D13-C)") (class "Default")
      (node (ref "D13") (pin "2") (pinfunction "C_2") (pintype "passive"))
      (node (ref "J5") (pin "3") (pinfunction "3_3") (pintype "passive"))
    )
    (net (code "66") (name "Net-(D14-A)") (class "Default")
      (node (ref "D14") (pin "1") (pinfunction "A_1") (pintype "passive"))
      (node (ref "J8") (pin "2") (pinfunction "2_2") (pintype "passive"))
      (node (ref "LED7") (pin "2") (pinfunction "C_2") (pintype "passive"))
      (node (ref "Q3") (pin "7") (pinfunction "D2_7") (pintype "passive"))
      (node (ref "Q3") (pin "8") (pinfunction "D2_8") (pintype "passive"))
    )
    (net (code "67") (name "Net-(D15-A)") (class "Default")
      (node (ref "D15") (pin "1") (pinfunction "A_1") (pintype "passive"))
      (node (ref "J9") (pin "2") (pinfunction "2_2") (pintype "passive"))
      (node (ref "LED8") (pin "2") (pinfunction "C_2") (pintype "passive"))
      (node (ref "Q4") (pin "7") (pinfunction "D2_7") (pintype "passive"))
      (node (ref "Q4") (pin "8") (pinfunction "D2_8") (pintype "passive"))
    )
    (net (code "68") (name "Net-(D16-C)") (class "Default")
      (node (ref "D16") (pin "2") (pinfunction "C_2") (pintype "passive"))
      (node (ref "J8") (pin "3") (pinfunction "3_3") (pintype "passive"))
    )
    (net (code "69") (name "Net-(D17-C)") (class "Default")
      (node (ref "D17") (pin "2") (pinfunction "C_2") (pintype "passive"))
      (node (ref "J9") (pin "3") (pinfunction "3_3") (pintype "passive"))
    )
    (net (code "70") (name "Net-(D18-A)") (class "Default")
      (node (ref "D18") (pin "1") (pinfunction "A_1") (pintype "passive"))
      (node (ref "J12") (pin "2") (pinfunction "2_2") (pintype "passive"))
      (node (ref "LED9") (pin "2") (pinfunction "C_2") (pintype "passive"))
      (node (ref "Q5") (pin "5") (pinfunction "D1_5") (pintype "passive"))
      (node (ref "Q5") (pin "6") (pinfunction "D1_6") (pintype "passive"))
    )
    (net (code "71") (name "Net-(D19-A)") (class "Default")
      (node (ref "D19") (pin "1") (pinfunction "A_1") (pintype "passive"))
      (node (ref "J17") (pin "2") (pinfunction "2_2") (pintype "passive"))
      (node (ref "LED10") (pin "2") (pinfunction "C_2") (pintype "passive"))
      (node (ref "Q6") (pin "5") (pinfunction "D1_5") (pintype "passive"))
      (node (ref "Q6") (pin "6") (pinfunction "D1_6") (pintype "passive"))
    )
    (net (code "72") (name "Net-(D20-A)") (class "Default")
      (node (ref "D20") (pin "1") (pinfunction "A_1") (pintype "passive"))
      (node (ref "J18") (pin "2") (pinfunction "2_2") (pintype "passive"))
      (node (ref "LED11") (pin "2") (pinfunction "C_2") (pintype "passive"))
      (node (ref "Q7") (pin "5") (pinfunction "D1_5") (pintype "passive"))
      (node (ref "Q7") (pin "6") (pinfunction "D1_6") (pintype "passive"))
    )
    (net (code "73") (name "Net-(D21-A)") (class "Default")
      (node (ref "D21") (pin "1") (pinfunction "A_1") (pintype "passive"))
      (node (ref "J13") (pin "2") (pinfunction "2_2") (pintype "passive"))
      (node (ref "LED12") (pin "2") (pinfunction "C_2") (pintype "passive"))
      (node (ref "Q8") (pin "5") (pinfunction "D1_5") (pintype "passive"))
      (node (ref "Q8") (pin "6") (pinfunction "D1_6") (pintype "passive"))
    )
    (net (code "74") (name "Net-(D22-A)") (class "Default")
      (node (ref "D22") (pin "1") (pinfunction "A_1") (pintype "passive"))
      (node (ref "J19") (pin "2") (pinfunction "2_2") (pintype "passive"))
      (node (ref "LED13") (pin "2") (pinfunction "C_2") (pintype "passive"))
      (node (ref "Q9") (pin "5") (pinfunction "D1_5") (pintype "passive"))
      (node (ref "Q9") (pin "6") (pinfunction "D1_6") (pintype "passive"))
    )
    (net (code "75") (name "Net-(D23-C)") (class "Default")
      (node (ref "D23") (pin "2") (pinfunction "C_2") (pintype "passive"))
      (node (ref "J12") (pin "3") (pinfunction "3_3") (pintype "passive"))
    )
    (net (code "76") (name "Net-(D24-C)") (class "Default")
      (node (ref "D24") (pin "2") (pinfunction "C_2") (pintype "passive"))
      (node (ref "J17") (pin "3") (pinfunction "3_3") (pintype "passive"))
    )
    (net (code "77") (name "Net-(D25-C)") (class "Default")
      (node (ref "D25") (pin "2") (pinfunction "C_2") (pintype "passive"))
      (node (ref "J18") (pin "3") (pinfunction "3_3") (pintype "passive"))
    )
    (net (code "78") (name "Net-(D26-C)") (class "Default")
      (node (ref "D26") (pin "2") (pinfunction "C_2") (pintype "passive"))
      (node (ref "J13") (pin "3") (pinfunction "3_3") (pintype "passive"))
    )
    (net (code "79") (name "Net-(D27-C)") (class "Default")
      (node (ref "D27") (pin "2") (pinfunction "C_2") (pintype "passive"))
      (node (ref "J19") (pin "3") (pinfunction "3_3") (pintype "passive"))
    )
    (net (code "80") (name "Net-(D28-A)") (class "Default")
      (node (ref "D28") (pin "1") (pinfunction "A_1") (pintype "passive"))
      (node (ref "J15") (pin "2") (pinfunction "2_2") (pintype "passive"))
      (node (ref "LED14") (pin "2") (pinfunction "C_2") (pintype "passive"))
      (node (ref "Q5") (pin "7") (pinfunction "D2_7") (pintype "passive"))
      (node (ref "Q5") (pin "8") (pinfunction "D2_8") (pintype "passive"))
    )
    (net (code "81") (name "Net-(D29-A)") (class "Default")
      (node (ref "D29") (pin "1") (pinfunction "A_1") (pintype "passive"))
      (node (ref "J20") (pin "2") (pinfunction "2_2") (pintype "passive"))
      (node (ref "LED15") (pin "2") (pinfunction "C_2") (pintype "passive"))
      (node (ref "Q6") (pin "7") (pinfunction "D2_7") (pintype "passive"))
      (node (ref "Q6") (pin "8") (pinfunction "D2_8") (pintype "passive"))
    )
    (net (code "82") (name "Net-(D30-A)") (class "Default")
      (node (ref "D30") (pin "1") (pinfunction "A_1") (pintype "passive"))
      (node (ref "J21") (pin "2") (pinfunction "2_2") (pintype "passive"))
      (node (ref "LED16") (pin "2") (pinfunction "C_2") (pintype "passive"))
      (node (ref "Q7") (pin "7") (pinfunction "D2_7") (pintype "passive"))
      (node (ref "Q7") (pin "8") (pinfunction "D2_8") (pintype "passive"))
    )
    (net (code "83") (name "Net-(D31-A)") (class "Default")
      (node (ref "D31") (pin "1") (pinfunction "A_1") (pintype "passive"))
      (node (ref "J16") (pin "2") (pinfunction "2_2") (pintype "passive"))
      (node (ref "LED17") (pin "2") (pinfunction "C_2") (pintype "passive"))
      (node (ref "Q8") (pin "7") (pinfunction "D2_7") (pintype "passive"))
      (node (ref "Q8") (pin "8") (pinfunction "D2_8") (pintype "passive"))
    )
    (net (code "84") (name "Net-(D32-A)") (class "Default")
      (node (ref "D32") (pin "1") (pinfunction "A_1") (pintype "passive"))
      (node (ref "J22") (pin "2") (pinfunction "2_2") (pintype "passive"))
      (node (ref "LED18") (pin "2") (pinfunction "C_2") (pintype "passive"))
      (node (ref "Q9") (pin "7") (pinfunction "D2_7") (pintype "passive"))
      (node (ref "Q9") (pin "8") (pinfunction "D2_8") (pintype "passive"))
    )
    (net (code "85") (name "Net-(D33-C)") (class "Default")
      (node (ref "D33") (pin "2") (pinfunction "C_2") (pintype "passive"))
      (node (ref "J15") (pin "3") (pinfunction "3_3") (pintype "passive"))
    )
    (net (code "86") (name "Net-(D34-C)") (class "Default")
      (node (ref "D34") (pin "2") (pinfunction "C_2") (pintype "passive"))
      (node (ref "J20") (pin "3") (pinfunction "3_3") (pintype "passive"))
    )
    (net (code "87") (name "Net-(D35-C)") (class "Default")
      (node (ref "D35") (pin "2") (pinfunction "C_2") (pintype "passive"))
      (node (ref "J21") (pin "3") (pinfunction "3_3") (pintype "passive"))
    )
    (net (code "88") (name "Net-(D36-C)") (class "Default")
      (node (ref "D36") (pin "2") (pinfunction "C_2") (pintype "passive"))
      (node (ref "J16") (pin "3") (pinfunction "3_3") (pintype "passive"))
    )
    (net (code "89") (name "Net-(D37-C)") (class "Default")
      (node (ref "D37") (pin "2") (pinfunction "C_2") (pintype "passive"))
      (node (ref "J22") (pin "3") (pinfunction "3_3") (pintype "passive"))
    )
    (net (code "90") (name "Net-(D38-A)") (class "Default")
      (node (ref "D38") (pin "1") (pinfunction "A_1") (pintype "passive"))
      (node (ref "J11") (pin "2") (pinfunction "2_2") (pintype "passive"))
      (node (ref "LED19") (pin "2") (pinfunction "C_2") (pintype "passive"))
      (node (ref "Q10") (pin "5") (pinfunction "D1_5") (pintype "passive"))
      (node (ref "Q10") (pin "6") (pinfunction "D1_6") (pintype "passive"))
    )
    (net (code "91") (name "Net-(D39-C)") (class "Default")
      (node (ref "D39") (pin "2") (pinfunction "C_2") (pintype "passive"))
      (node (ref "J11") (pin "3") (pinfunction "3_3") (pintype "passive"))
    )
    (net (code "92") (name "Net-(D40-A)") (class "Default")
      (node (ref "D40") (pin "1") (pinfunction "A_1") (pintype "passive"))
      (node (ref "J14") (pin "2") (pinfunction "2_2") (pintype "passive"))
      (node (ref "LED20") (pin "2") (pinfunction "C_2") (pintype "passive"))
      (node (ref "Q10") (pin "7") (pinfunction "D2_7") (pintype "passive"))
      (node (ref "Q10") (pin "8") (pinfunction "D2_8") (pintype "passive"))
    )
    (net (code "93") (name "Net-(D41-C)") (class "Default")
      (node (ref "D41") (pin "2") (pinfunction "C_2") (pintype "passive"))
      (node (ref "J14") (pin "3") (pinfunction "3_3") (pintype "passive"))
    )
    (net (code "94") (name "Net-(J2-Pad2)") (class "Default")
      (node (ref "J2") (pin "2") (pinfunction "2_2") (pintype "passive"))
      (node (ref "R7") (pin "1") (pinfunction "1_1") (pintype "passive"))
    )
    (net (code "95") (name "Net-(J2-Pad3)") (class "Default")
      (node (ref "J2") (pin "3") (pinfunction "3_3") (pintype "passive"))
      (node (ref "R8") (pin "1") (pinfunction "1_1") (pintype "passive"))
    )
    (net (code "96") (name "Net-(J6-Pad1)") (class "Default")
      (node (ref "J6") (pin "1") (pinfunction "1_1") (pintype "passive"))
      (node (ref "R12") (pin "2") (pinfunction "2_2") (pintype "passive"))
    )
    (net (code "97") (name "Net-(LED1-A)") (class "Default")
      (node (ref "LED1") (pin "1") (pinfunction "A_1") (pintype "passive"))
      (node (ref "R9") (pin "1") (pinfunction "1_1") (pintype "passive"))
    )
    (net (code "98") (name "Net-(LED2-A)") (class "Default")
      (node (ref "LED2") (pin "1") (pinfunction "A_1") (pintype "passive"))
      (node (ref "R11") (pin "1") (pinfunction "1_1") (pintype "passive"))
    )
    (net (code "99") (name "Net-(LED3-A)") (class "Default")
      (node (ref "LED3") (pin "1") (pinfunction "A_1") (pintype "passive"))
      (node (ref "R13") (pin "1") (pinfunction "1_1") (pintype "passive"))
    )
    (net (code "100") (name "Net-(LED4-A)") (class "Default")
      (node (ref "LED4") (pin "1") (pinfunction "A_1") (pintype "passive"))
      (node (ref "R48") (pin "1") (pinfunction "1_1") (pintype "passive"))
    )
    (net (code "101") (name "Net-(LED5-A)") (class "Default")
      (node (ref "LED5") (pin "1") (pinfunction "A_1") (pintype "passive"))
      (node (ref "R18") (pin "1") (pinfunction "1_1") (pintype "passive"))
    )
    (net (code "102") (name "Net-(LED6-A)") (class "Default")
      (node (ref "LED6") (pin "1") (pinfunction "A_1") (pintype "passive"))
      (node (ref "R15") (pin "1") (pinfunction "1_1") (pintype "passive"))
    )
    (net (code "103") (name "Net-(LED7-A)") (class "Default")
      (node (ref "LED7") (pin "1") (pinfunction "A_1") (pintype "passive"))
      (node (ref "R21") (pin "1") (pinfunction "1_1") (pintype "passive"))
    )
    (net (code "104") (name "Net-(LED8-A)") (class "Default")
      (node (ref "LED8") (pin "1") (pinfunction "A_1") (pintype "passive"))
      (node (ref "R17") (pin "1") (pinfunction "1_1") (pintype "passive"))
    )
    (net (code "105") (name "Net-(LED9-A)") (class "Default")
      (node (ref "LED9") (pin "1") (pinfunction "A_1") (pintype "passive"))
      (node (ref "R22") (pin "1") (pinfunction "1_1") (pintype "passive"))
    )
    (net (code "106") (name "Net-(LED10-A)") (class "Default")
      (node (ref "LED10") (pin "1") (pinfunction "A_1") (pintype "passive"))
      (node (ref "R23") (pin "1") (pinfunction "1_1") (pintype "passive"))
    )
    (net (code "107") (name "Net-(LED11-A)") (class "Default")
      (node (ref "LED11") (pin "1") (pinfunction "A_1") (pintype "passive"))
      (node (ref "R24") (pin "1") (pinfunction "1_1") (pintype "passive"))
    )
    (net (code "108") (name "Net-(LED12-A)") (class "Default")
      (node (ref "LED12") (pin "1") (pinfunction "A_1") (pintype "passive"))
      (node (ref "R25") (pin "1") (pinfunction "1_1") (pintype "passive"))
    )
    (net (code "109") (name "Net-(LED13-A)") (class "Default")
      (node (ref "LED13") (pin "1") (pinfunction "A_1") (pintype "passive"))
      (node (ref "R26") (pin "1") (pinfunction "1_1") (pintype "passive"))
    )
    (net (code "110") (name "Net-(LED14-A)") (class "Default")
      (node (ref "LED14") (pin "1") (pinfunction "A_1") (pintype "passive"))
      (node (ref "R39") (pin "1") (pinfunction "1_1") (pintype "passive"))
    )
    (net (code "111") (name "Net-(LED15-A)") (class "Default")
      (node (ref "LED15") (pin "1") (pinfunction "A_1") (pintype "passive"))
      (node (ref "R40") (pin "1") (pinfunction "1_1") (pintype "passive"))
    )
    (net (code "112") (name "Net-(LED16-A)") (class "Default")
      (node (ref "LED16") (pin "1") (pinfunction "A_1") (pintype "passive"))
      (node (ref "R41") (pin "1") (pinfunction "1_1") (pintype "passive"))
    )
    (net (code "113") (name "Net-(LED17-A)") (class "Default")
      (node (ref "LED17") (pin "1") (pinfunction "A_1") (pintype "passive"))
      (node (ref "R42") (pin "1") (pinfunction "1_1") (pintype "passive"))
    )
    (net (code "114") (name "Net-(LED18-A)") (class "Default")
      (node (ref "LED18") (pin "1") (pinfunction "A_1") (pintype "passive"))
      (node (ref "R43") (pin "1") (pinfunction "1_1") (pintype "passive"))
    )
    (net (code "115") (name "Net-(LED19-A)") (class "Default")
      (node (ref "LED19") (pin "1") (pinfunction "A_1") (pintype "passive"))
      (node (ref "R44") (pin "1") (pinfunction "1_1") (pintype "passive"))
    )
    (net (code "116") (name "Net-(LED20-A)") (class "Default")
      (node (ref "LED20") (pin "1") (pinfunction "A_1") (pintype "passive"))
      (node (ref "R47") (pin "1") (pinfunction "1_1") (pintype "passive"))
    )
    (net (code "117") (name "Net-(LED21-A)") (class "Default")
      (node (ref "LED21") (pin "1") (pinfunction "A_1") (pintype "passive"))
      (node (ref "R49") (pin "1") (pinfunction "1_1") (pintype "passive"))
    )
    (net (code "118") (name "Net-(LED22-A)") (class "Default")
      (node (ref "LED22") (pin "1") (pinfunction "A_1") (pintype "passive"))
      (node (ref "R50") (pin "1") (pinfunction "1_1") (pintype "passive"))
    )
    (net (code "119") (name "Net-(LED23-A)") (class "Default")
      (node (ref "LED23") (pin "1") (pinfunction "A_1") (pintype "passive"))
      (node (ref "R51") (pin "1") (pinfunction "1_1") (pintype "passive"))
    )
    (net (code "120") (name "Net-(LED24-A)") (class "Default")
      (node (ref "LED24") (pin "1") (pinfunction "A_1") (pintype "passive"))
      (node (ref "R52") (pin "1") (pinfunction "1_1") (pintype "passive"))
    )
    (net (code "121") (name "Net-(LED25-A)") (class "Default")
      (node (ref "LED25") (pin "1") (pinfunction "A_1") (pintype "passive"))
      (node (ref "R53") (pin "1") (pinfunction "1_1") (pintype "passive"))
    )
    (net (code "122") (name "Net-(Q1-G1)") (class "Default")
      (node (ref "Q1") (pin "4") (pinfunction "G1_4") (pintype "passive"))
      (node (ref "R30") (pin "2") (pinfunction "2_2") (pintype "passive"))
    )
    (net (code "123") (name "Net-(Q1-G2)") (class "Default")
      (node (ref "Q1") (pin "2") (pinfunction "G2_2") (pintype "passive"))
      (node (ref "R31") (pin "1") (pinfunction "1_1") (pintype "passive"))
    )
    (net (code "124") (name "Net-(Q3-G1)") (class "Default")
      (node (ref "Q3") (pin "4") (pinfunction "G1_4") (pintype "passive"))
      (node (ref "R19") (pin "2") (pinfunction "2_2") (pintype "passive"))
    )
    (net (code "125") (name "Net-(Q3-G2)") (class "Default")
      (node (ref "Q3") (pin "2") (pinfunction "G2_2") (pintype "passive"))
      (node (ref "R20") (pin "2") (pinfunction "2_2") (pintype "passive"))
    )
    (net (code "126") (name "Net-(Q4-G1)") (class "Default")
      (node (ref "Q4") (pin "4") (pinfunction "G1_4") (pintype "passive"))
      (node (ref "R14") (pin "2") (pinfunction "2_2") (pintype "passive"))
    )
    (net (code "127") (name "Net-(Q4-G2)") (class "Default")
      (node (ref "Q4") (pin "2") (pinfunction "G2_2") (pintype "passive"))
      (node (ref "R16") (pin "2") (pinfunction "2_2") (pintype "passive"))
    )
    (net (code "128") (name "Net-(Q5-G1)") (class "Default")
      (node (ref "Q5") (pin "4") (pinfunction "G1_4") (pintype "passive"))
      (node (ref "R27") (pin "2") (pinfunction "2_2") (pintype "passive"))
    )
    (net (code "129") (name "Net-(Q5-G2)") (class "Default")
      (node (ref "Q5") (pin "2") (pinfunction "G2_2") (pintype "passive"))
      (node (ref "R34") (pin "2") (pinfunction "2_2") (pintype "passive"))
    )
    (net (code "130") (name "Net-(Q6-G1)") (class "Default")
      (node (ref "Q6") (pin "4") (pinfunction "G1_4") (pintype "passive"))
      (node (ref "R28") (pin "2") (pinfunction "2_2") (pintype "passive"))
    )
    (net (code "131") (name "Net-(Q6-G2)") (class "Default")
      (node (ref "Q6") (pin "2") (pinfunction "G2_2") (pintype "passive"))
      (node (ref "R35") (pin "2") (pinfunction "2_2") (pintype "passive"))
    )
    (net (code "132") (name "Net-(Q7-G1)") (class "Default")
      (node (ref "Q7") (pin "4") (pinfunction "G1_4") (pintype "passive"))
      (node (ref "R29") (pin "2") (pinfunction "2_2") (pintype "passive"))
    )
    (net (code "133") (name "Net-(Q7-G2)") (class "Default")
      (node (ref "Q7") (pin "2") (pinfunction "G2_2") (pintype "passive"))
      (node (ref "R36") (pin "2") (pinfunction "2_2") (pintype "passive"))
    )
    (net (code "134") (name "Net-(Q8-G1)") (class "Default")
      (node (ref "Q8") (pin "4") (pinfunction "G1_4") (pintype "passive"))
      (node (ref "R32") (pin "2") (pinfunction "2_2") (pintype "passive"))
    )
    (net (code "135") (name "Net-(Q8-G2)") (class "Default")
      (node (ref "Q8") (pin "2") (pinfunction "G2_2") (pintype "passive"))
      (node (ref "R37") (pin "2") (pinfunction "2_2") (pintype "passive"))
    )
    (net (code "136") (name "Net-(Q9-G1)") (class "Default")
      (node (ref "Q9") (pin "4") (pinfunction "G1_4") (pintype "passive"))
      (node (ref "R33") (pin "2") (pinfunction "2_2") (pintype "passive"))
    )
    (net (code "137") (name "Net-(Q9-G2)") (class "Default")
      (node (ref "Q9") (pin "2") (pinfunction "G2_2") (pintype "passive"))
      (node (ref "R38") (pin "2") (pinfunction "2_2") (pintype "passive"))
    )
    (net (code "138") (name "Net-(Q10-G1)") (class "Default")
      (node (ref "Q10") (pin "4") (pinfunction "G1_4") (pintype "passive"))
      (node (ref "R45") (pin "2") (pinfunction "2_2") (pintype "passive"))
    )
    (net (code "139") (name "Net-(Q10-G2)") (class "Default")
      (node (ref "Q10") (pin "2") (pinfunction "G2_2") (pintype "passive"))
      (node (ref "R46") (pin "2") (pinfunction "2_2") (pintype "passive"))
    )
    (net (code "140") (name "Net-(U1-P3.2{slash}INT0{slash}SCLK_4{slash}SCL_4{slash}PWMETI{slash}PWMETI2)") (class "Default")
      (node (ref "SW1") (pin "10") (pinfunction "10_10") (pintype "passive"))
      (node (ref "U1") (pin "29") (pinfunction "P3.2/INT0/SCLK_4/SCL_4/PWMETI/PWMETI2_29") (pintype "passive"))
    )
    (net (code "141") (name "Net-(U1-P3.3{slash}INT1{slash}MISO_4{slash}SDA_4{slash}PWM4N_4{slash}PWM7_2)") (class "Default")
      (node (ref "SW1") (pin "9") (pinfunction "9_9") (pintype "passive"))
      (node (ref "U1") (pin "30") (pinfunction "P3.3/INT1/MISO_4/SDA_4/PWM4N_4/PWM7_2_30") (pintype "passive"))
    )
    (net (code "142") (name "Net-(U1-P3.4{slash}T0{slash}T1CLKO{slash}MOSI_4{slash}PWM4P_4{slash}PWM8_2{slash}CMPO)") (class "Default")
      (node (ref "SW1") (pin "8") (pinfunction "8_8") (pintype "passive"))
      (node (ref "U1") (pin "31") (pinfunction "P3.4/T0/T1CLKO/MOSI_4/PWM4P_4/PWM8_2/CMPO_31") (pintype "passive"))
    )
    (net (code "143") (name "Net-(U1-P5.0{slash}RxD3_2{slash}CMP+_2)") (class "Default")
      (node (ref "SW1") (pin "7") (pinfunction "7_7") (pintype "passive"))
      (node (ref "U1") (pin "32") (pinfunction "P5.0/RxD3_2/CMP+_2_32") (pintype "passive"))
    )
    (net (code "144") (name "Net-(U1-P5.1{slash}TxD3_2{slash}CMP+_3)") (class "Default")
      (node (ref "SW1") (pin "6") (pinfunction "6_6") (pintype "passive"))
      (node (ref "U1") (pin "33") (pinfunction "P5.1/TxD3_2/CMP+_3_33") (pintype "passive"))
    )
    (net (code "145") (name "Net-(U1-UCap)") (class "Default")
      (node (ref "C1") (pin "1") (pinfunction "1_1") (pintype "passive"))
      (node (ref "U1") (pin "17") (pinfunction "UCap_17") (pintype "passive"))
    )
    (net (code "146") (name "Net-(U2-A)") (class "Default")
      (node (ref "R2") (pin "2") (pinfunction "2_2") (pintype "passive"))
      (node (ref "U2") (pin "6") (pinfunction "A_6") (pintype "passive"))
    )
    (net (code "147") (name "Net-(U2-B)") (class "Default")
      (node (ref "R1") (pin "2") (pinfunction "2_2") (pintype "passive"))
      (node (ref "U2") (pin "7") (pinfunction "B_7") (pintype "passive"))
    )
    (net (code "148") (name "Net-(U2-DI)") (class "Default")
      (node (ref "R4") (pin "1") (pinfunction "1_1") (pintype "passive"))
      (node (ref "U2") (pin "4") (pinfunction "DI_4") (pintype "passive"))
    )
    (net (code "149") (name "Net-(U2-RO)") (class "Default")
      (node (ref "R3") (pin "1") (pinfunction "1_1") (pintype "passive"))
      (node (ref "U2") (pin "1") (pinfunction "RO_1") (pintype "passive"))
    )
    (net (code "150") (name "Net-(U3-BST)") (class "Default")
      (node (ref "C5") (pin "2") (pinfunction "2_2") (pintype "passive"))
      (node (ref "U3") (pin "1") (pinfunction "BST_1") (pintype "passive"))
    )
    (net (code "151") (name "Net-(U3-SW)") (class "Default")
      (node (ref "C5") (pin "1") (pinfunction "1_1") (pintype "passive"))
      (node (ref "L3") (pin "1") (pinfunction "1_1") (pintype "passive"))
      (node (ref "U3") (pin "6") (pinfunction "SW_6") (pintype "passive"))
    )
    (net (code "152") (name "unconnected-(J6-Pad3)") (class "Default")
      (node (ref "J6") (pin "3") (pinfunction "3_3") (pintype "passive+no_connect"))
    )
    (net (code "153") (name "unconnected-(J24-Pad1)") (class "Default")
      (node (ref "J24") (pin "1") (pinfunction "1_1") (pintype "passive"))
    )
    (net (code "154") (name "unconnected-(J24-Pad6)") (class "Default")
      (node (ref "J24") (pin "6") (pinfunction "6_6") (pintype "passive"))
    )
    (net (code "155") (name "unconnected-(J25-Pad1)") (class "Default")
      (node (ref "J25") (pin "1") (pinfunction "1_1") (pintype "passive"))
    )
    (net (code "156") (name "unconnected-(J25-Pad6)") (class "Default")
      (node (ref "J25") (pin "6") (pinfunction "6_6") (pintype "passive"))
    )
    (net (code "157") (name "unconnected-(U1-P3.7{slash}INT3{slash}TxD_2{slash}CMP+-Pad36)") (class "Default")
      (node (ref "U1") (pin "36") (pinfunction "P3.7/INT3/TxD_2/CMP+_36") (pintype "passive"))
    )
    (net (code "158") (name "unconnected-(U1-P4.1{slash}MISO_3{slash}CMPO_2{slash}PWMETI_2-Pad41)") (class "Default")
      (node (ref "U1") (pin "41") (pinfunction "P4.1/MISO_3/CMPO_2/PWMETI_2_41") (pintype "passive"))
    )
    (net (code "159") (name "unconnected-(U1-P4.2{slash}WR-Pad42)") (class "Default")
      (node (ref "U1") (pin "42") (pinfunction "P4.2/WR_42") (pintype "passive"))
    )
    (net (code "160") (name "unconnected-(U1-P4.3{slash}RxD_4{slash}SCLK_3-Pad43)") (class "Default")
      (node (ref "U1") (pin "43") (pinfunction "P4.3/RxD_4/SCLK_3_43") (pintype "passive"))
    )
    (net (code "161") (name "unconnected-(U1-P7.0-Pad37)") (class "Default")
      (node (ref "U1") (pin "37") (pinfunction "P7.0_37") (pintype "passive"))
    )
    (net (code "162") (name "unconnected-(U1-P7.1-Pad38)") (class "Default")
      (node (ref "U1") (pin "38") (pinfunction "P7.1_38") (pintype "passive"))
    )
    (net (code "163") (name "unconnected-(U1-P7.2-Pad39)") (class "Default")
      (node (ref "U1") (pin "39") (pinfunction "P7.2_39") (pintype "passive"))
    )
    (net (code "164") (name "unconnected-(U1-P7.3{slash}PWMETI_3-Pad40)") (class "Default")
      (node (ref "U1") (pin "40") (pinfunction "P7.3/PWMETI_3_40") (pintype "passive"))
    )
  )
)
